# zx80_SD_12_smd_build006_6_STM32.net
KiCad netlist of a schematic drawn in EAGLE
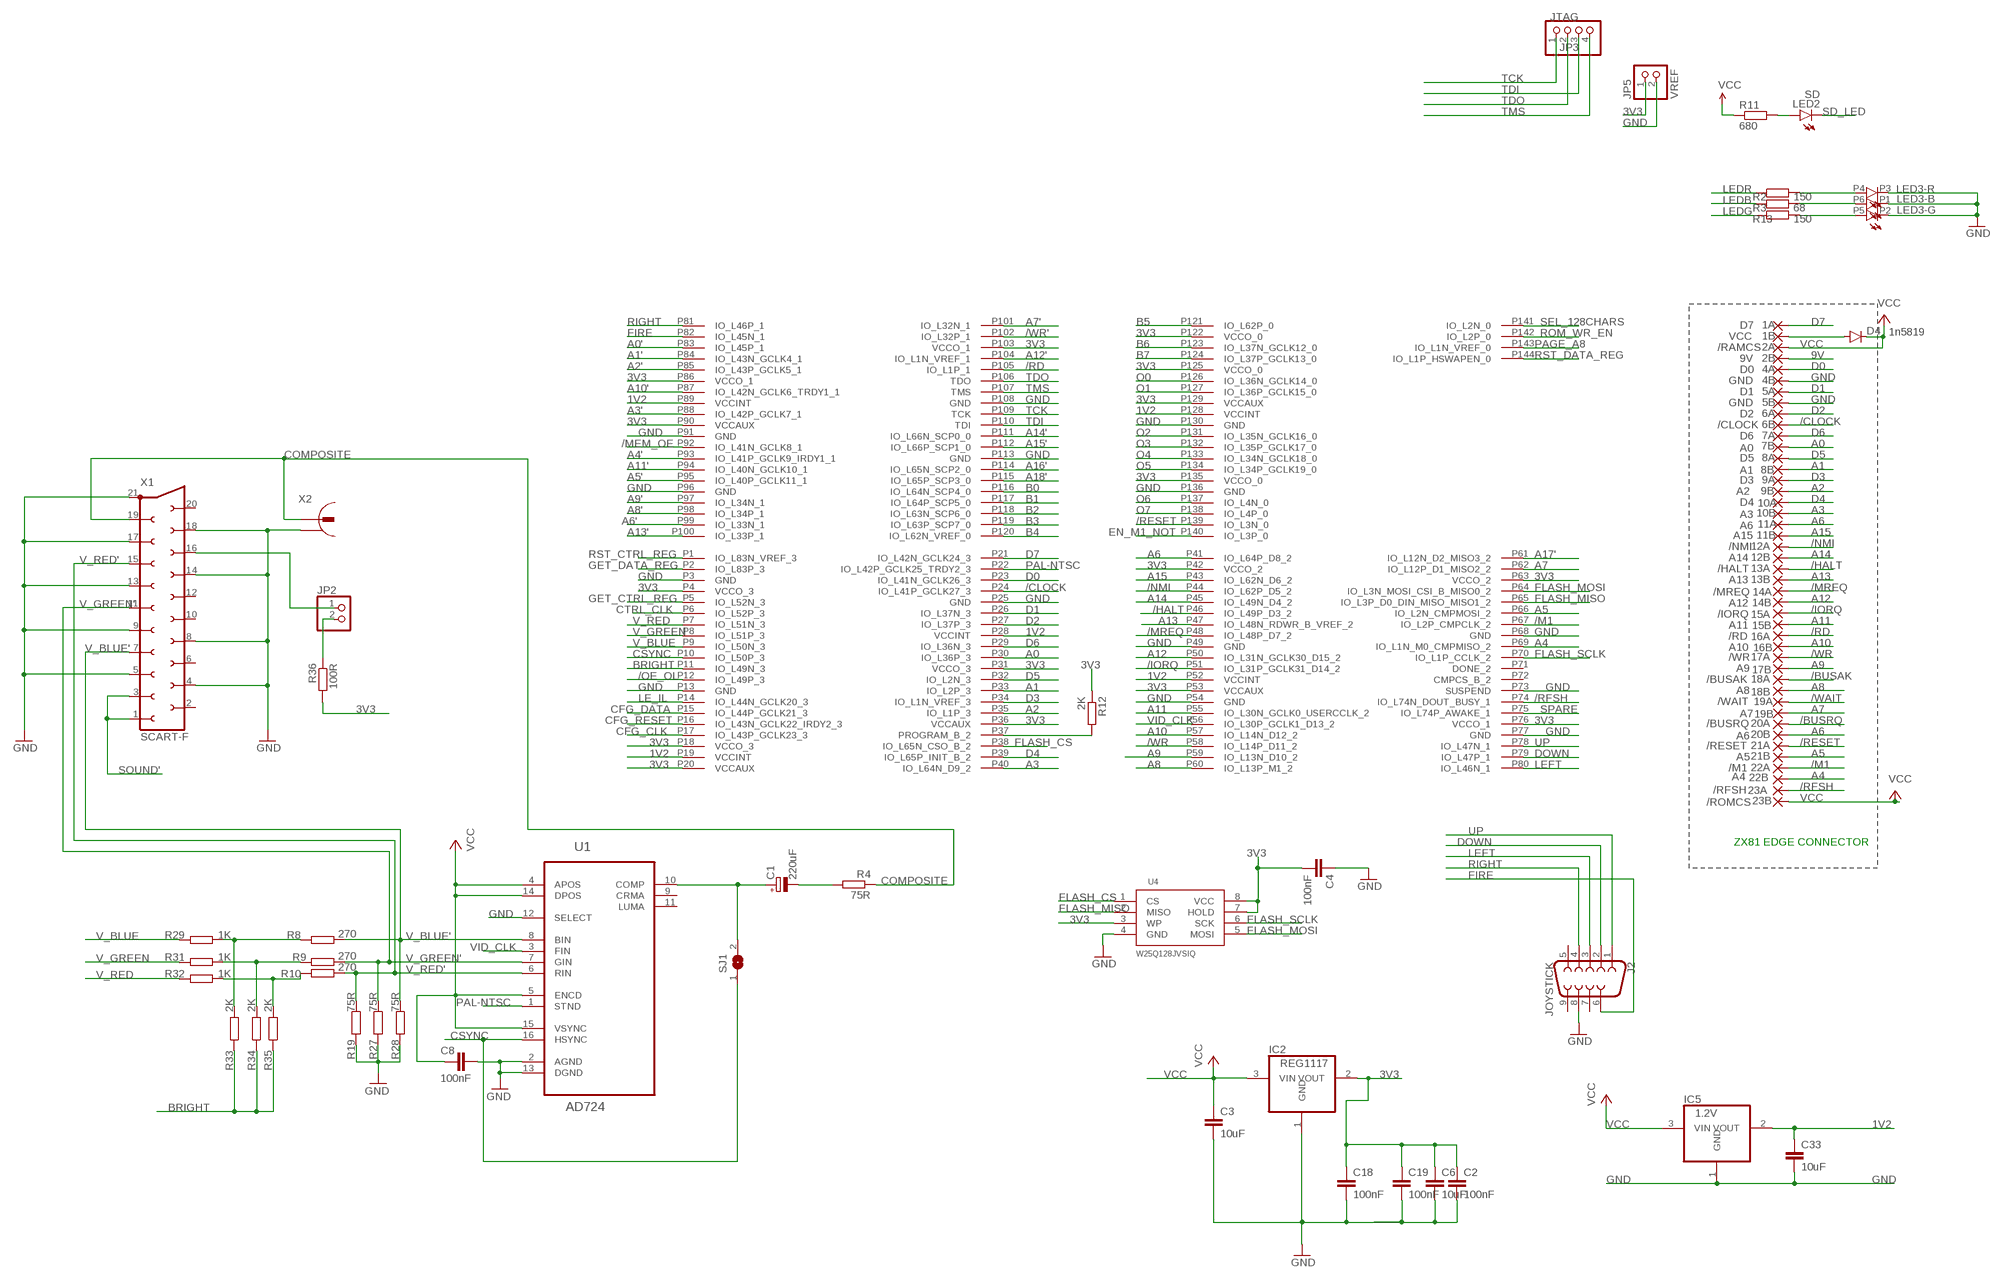
[diagram p0: schematic, sheet 1, part 1 of 2]
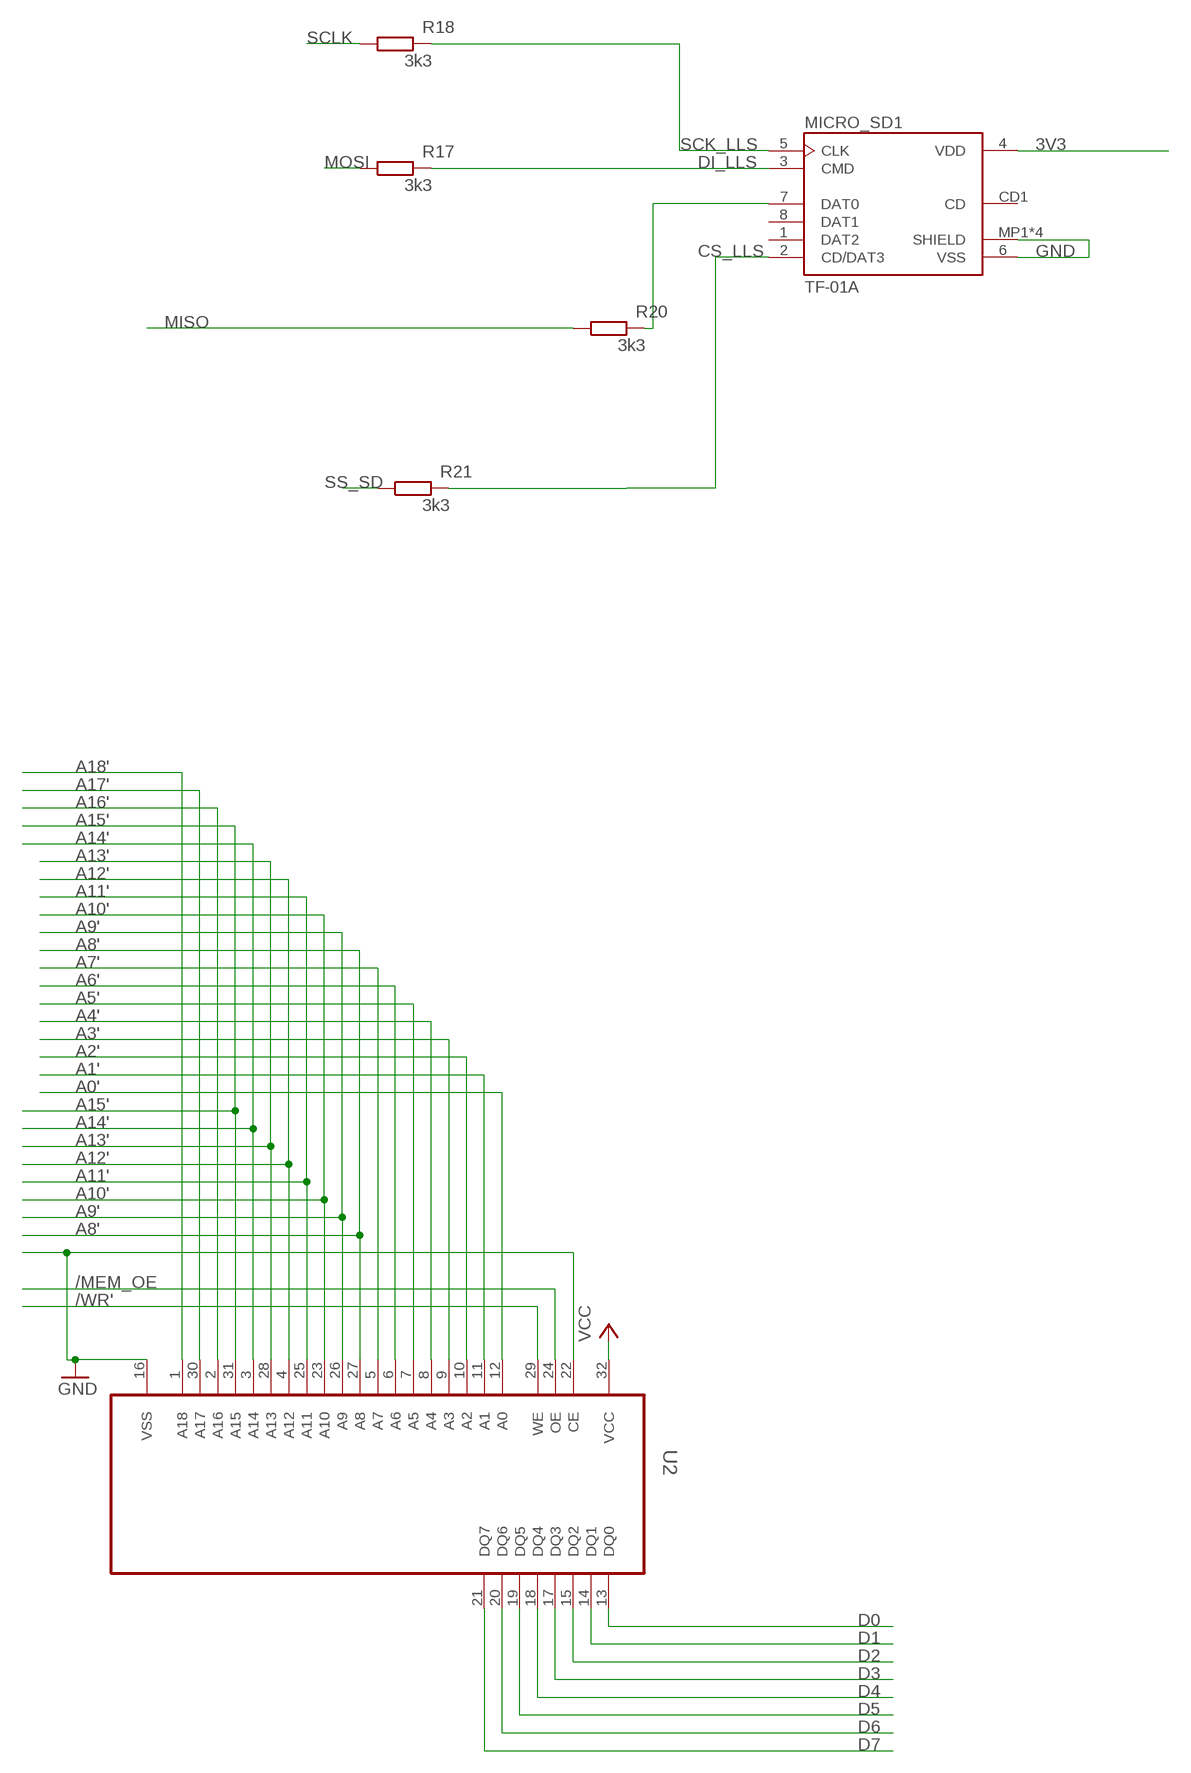
[diagram p1: schematic, sheet 1, part 2 of 2]
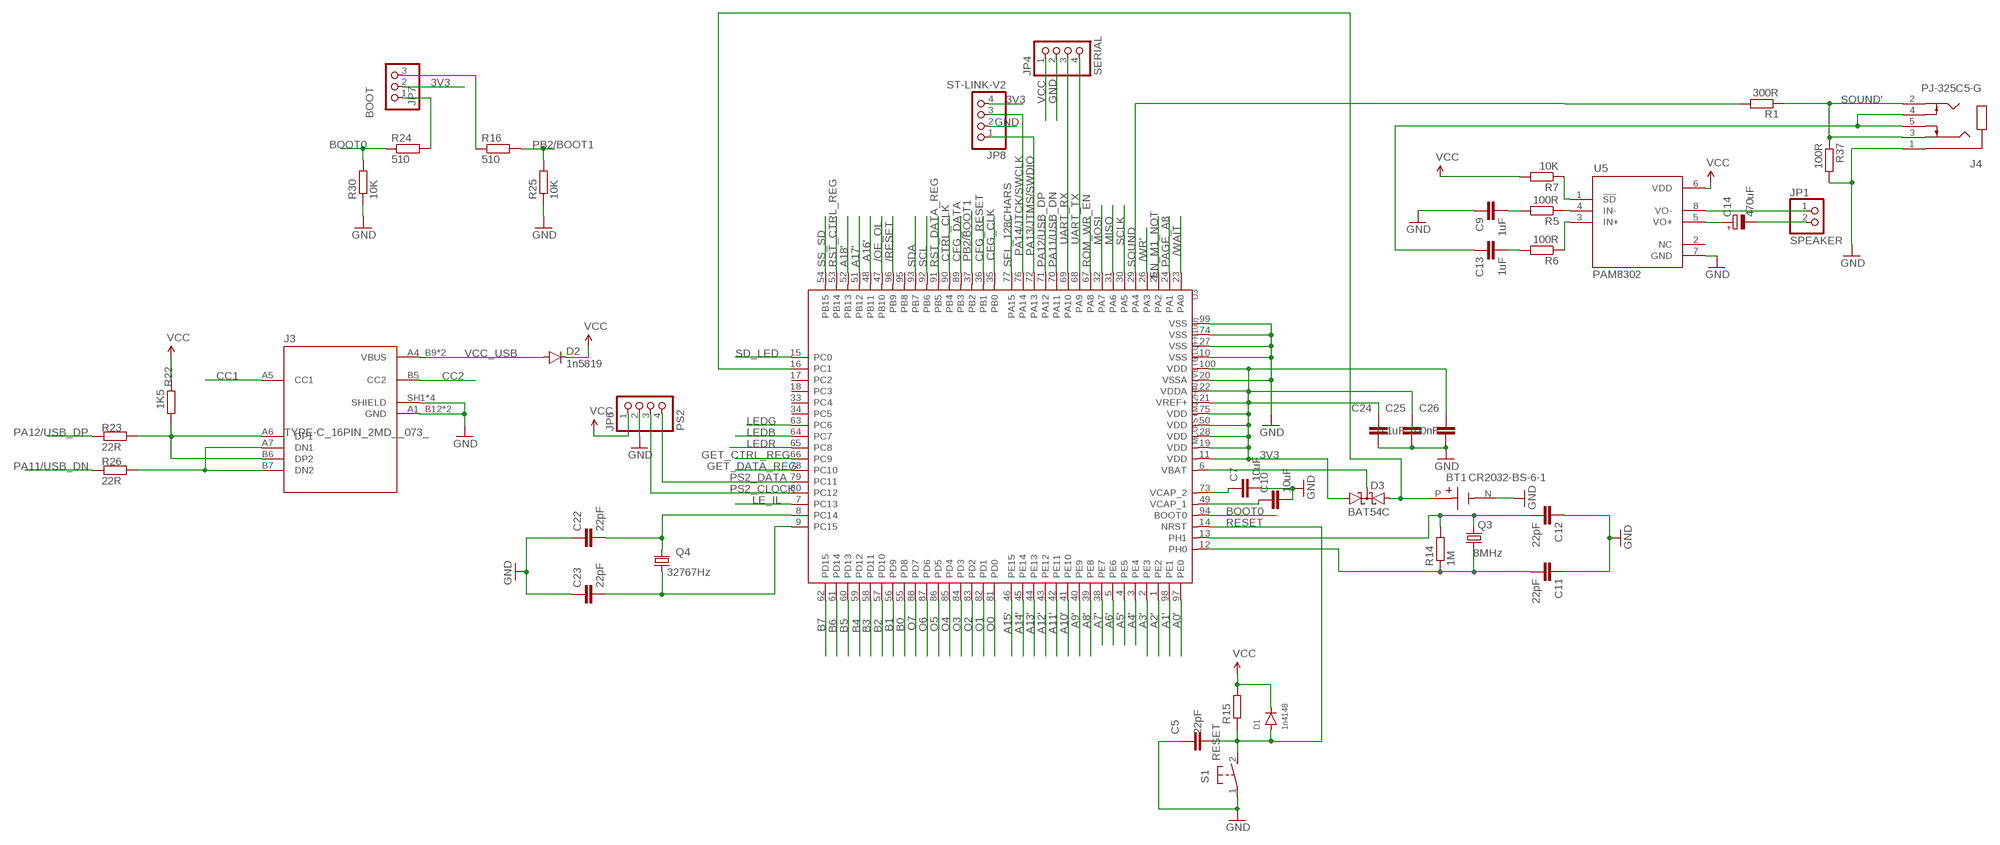
[diagram p2: schematic, sheet 2]

(export (version "E")
  (design (tool "Eeschema 10.0.6"))
  (components
    (comp (ref "1A")
      (value "D7")
      (footprint "eagle-import:EDGEPIN")
      (libsource (lib "eagle-import") (part "SMD2EDGEPIN"))
    )
    (comp (ref "1B")
      (value "VCC")
      (footprint "eagle-import:EDGEPIN")
      (libsource (lib "eagle-import") (part "SMD2EDGEPIN"))
    )
    (comp (ref "2A")
      (value "/RAMCS")
      (footprint "eagle-import:EDGEPIN")
      (libsource (lib "eagle-import") (part "SMD2EDGEPIN"))
    )
    (comp (ref "2B")
      (value "9V")
      (footprint "eagle-import:EDGEPIN")
      (libsource (lib "eagle-import") (part "SMD2EDGEPIN"))
    )
    (comp (ref "4A")
      (value "D0")
      (footprint "eagle-import:EDGEPIN")
      (libsource (lib "eagle-import") (part "SMD2EDGEPIN"))
    )
    (comp (ref "4B")
      (value "GND")
      (footprint "eagle-import:EDGEPIN")
      (libsource (lib "eagle-import") (part "SMD2EDGEPIN"))
    )
    (comp (ref "5A")
      (value "D1")
      (footprint "eagle-import:EDGEPIN")
      (libsource (lib "eagle-import") (part "SMD2EDGEPIN"))
    )
    (comp (ref "5B")
      (value "GND")
      (footprint "eagle-import:EDGEPIN")
      (libsource (lib "eagle-import") (part "SMD2EDGEPIN"))
    )
    (comp (ref "6A")
      (value "D2")
      (footprint "eagle-import:EDGEPIN")
      (libsource (lib "eagle-import") (part "SMD2EDGEPIN"))
    )
    (comp (ref "6B")
      (value "/CLOCK")
      (footprint "eagle-import:EDGEPIN")
      (libsource (lib "eagle-import") (part "SMD2EDGEPIN"))
    )
    (comp (ref "7A")
      (value "D6")
      (footprint "eagle-import:EDGEPIN")
      (libsource (lib "eagle-import") (part "SMD2EDGEPIN"))
    )
    (comp (ref "7B")
      (value "A0")
      (footprint "eagle-import:EDGEPIN")
      (libsource (lib "eagle-import") (part "SMD2EDGEPIN"))
    )
    (comp (ref "8A")
      (value "D5")
      (footprint "eagle-import:EDGEPIN")
      (libsource (lib "eagle-import") (part "SMD2EDGEPIN"))
    )
    (comp (ref "8B")
      (value "A1")
      (footprint "eagle-import:EDGEPIN")
      (libsource (lib "eagle-import") (part "SMD2EDGEPIN"))
    )
    (comp (ref "9A")
      (value "D3")
      (footprint "eagle-import:EDGEPIN")
      (libsource (lib "eagle-import") (part "SMD2EDGEPIN"))
    )
    (comp (ref "9B")
      (value "A2")
      (footprint "eagle-import:EDGEPIN")
      (libsource (lib "eagle-import") (part "SMD2EDGEPIN"))
    )
    (comp (ref "10A")
      (value "D4")
      (footprint "eagle-import:EDGEPIN")
      (libsource (lib "eagle-import") (part "SMD2EDGEPIN"))
    )
    (comp (ref "10B")
      (value "A3")
      (footprint "eagle-import:EDGEPIN")
      (libsource (lib "eagle-import") (part "SMD2EDGEPIN"))
    )
    (comp (ref "11A")
      (value "A6")
      (footprint "eagle-import:EDGEPIN")
      (libsource (lib "eagle-import") (part "SMD2EDGEPIN"))
    )
    (comp (ref "11B")
      (value "A15")
      (footprint "eagle-import:EDGEPIN")
      (libsource (lib "eagle-import") (part "SMD2EDGEPIN"))
    )
    (comp (ref "12A")
      (value "/NMI")
      (footprint "eagle-import:EDGEPIN")
      (libsource (lib "eagle-import") (part "SMD2EDGEPIN"))
    )
    (comp (ref "12B")
      (value "A14")
      (footprint "eagle-import:EDGEPIN")
      (libsource (lib "eagle-import") (part "SMD2EDGEPIN"))
    )
    (comp (ref "13A")
      (value "/HALT")
      (footprint "eagle-import:EDGEPIN")
      (libsource (lib "eagle-import") (part "SMD2EDGEPIN"))
    )
    (comp (ref "13B")
      (value "A13")
      (footprint "eagle-import:EDGEPIN")
      (libsource (lib "eagle-import") (part "SMD2EDGEPIN"))
    )
    (comp (ref "14A")
      (value "/MREQ")
      (footprint "eagle-import:EDGEPIN")
      (libsource (lib "eagle-import") (part "SMD2EDGEPIN"))
    )
    (comp (ref "14B")
      (value "A12")
      (footprint "eagle-import:EDGEPIN")
      (libsource (lib "eagle-import") (part "SMD2EDGEPIN"))
    )
    (comp (ref "15A")
      (value "/IORQ")
      (footprint "eagle-import:EDGEPIN")
      (libsource (lib "eagle-import") (part "SMD2EDGEPIN"))
    )
    (comp (ref "15B")
      (value "A11")
      (footprint "eagle-import:EDGEPIN")
      (libsource (lib "eagle-import") (part "SMD2EDGEPIN"))
    )
    (comp (ref "16A")
      (value "/RD")
      (footprint "eagle-import:EDGEPIN")
      (libsource (lib "eagle-import") (part "SMD2EDGEPIN"))
    )
    (comp (ref "16B")
      (value "A10")
      (footprint "eagle-import:EDGEPIN")
      (libsource (lib "eagle-import") (part "SMD2EDGEPIN"))
    )
    (comp (ref "17A")
      (value "/WR")
      (footprint "eagle-import:EDGEPIN")
      (libsource (lib "eagle-import") (part "SMD2EDGEPIN"))
    )
    (comp (ref "17B")
      (value "A9")
      (footprint "eagle-import:EDGEPIN")
      (libsource (lib "eagle-import") (part "SMD2EDGEPIN"))
    )
    (comp (ref "18A")
      (value "/BUSAK")
      (footprint "eagle-import:EDGEPIN")
      (libsource (lib "eagle-import") (part "SMD2EDGEPIN"))
    )
    (comp (ref "18B")
      (value "A8")
      (footprint "eagle-import:EDGEPIN")
      (libsource (lib "eagle-import") (part "SMD2EDGEPIN"))
    )
    (comp (ref "19A")
      (value "/WAIT")
      (footprint "eagle-import:EDGEPIN")
      (libsource (lib "eagle-import") (part "SMD2EDGEPIN"))
    )
    (comp (ref "19B")
      (value "A7")
      (footprint "eagle-import:EDGEPIN")
      (libsource (lib "eagle-import") (part "SMD2EDGEPIN"))
    )
    (comp (ref "20A")
      (value "/BUSRQ")
      (footprint "eagle-import:EDGEPIN")
      (libsource (lib "eagle-import") (part "SMD2EDGEPIN"))
    )
    (comp (ref "20B")
      (value "A6")
      (footprint "eagle-import:EDGEPIN")
      (libsource (lib "eagle-import") (part "SMD2EDGEPIN"))
    )
    (comp (ref "21A")
      (value "/RESET")
      (footprint "eagle-import:EDGEPIN")
      (libsource (lib "eagle-import") (part "SMD2EDGEPIN"))
    )
    (comp (ref "21B")
      (value "A5")
      (footprint "eagle-import:EDGEPIN")
      (libsource (lib "eagle-import") (part "SMD2EDGEPIN"))
    )
    (comp (ref "22A")
      (value "/M1")
      (footprint "eagle-import:EDGEPIN")
      (libsource (lib "eagle-import") (part "SMD2EDGEPIN"))
    )
    (comp (ref "22B")
      (value "A4")
      (footprint "eagle-import:EDGEPIN")
      (libsource (lib "eagle-import") (part "SMD2EDGEPIN"))
    )
    (comp (ref "23A")
      (value "/RFSH")
      (footprint "eagle-import:EDGEPIN")
      (libsource (lib "eagle-import") (part "SMD2EDGEPIN"))
    )
    (comp (ref "23B")
      (value "/ROMCS")
      (footprint "eagle-import:EDGEPIN")
      (libsource (lib "eagle-import") (part "SMD2EDGEPIN"))
    )
    (comp (ref "C1")
      (value "220uF")
      (footprint "eagle-import:UD-6,3X7,7_NICHICON")
      (libsource (lib "eagle-import") (part "CPOL-EUUD-6,3X7,7"))
    )
    (comp (ref "C2")
      (value "100nF")
      (footprint "eagle-import:C0603")
      (libsource (lib "eagle-import") (part "C-EUC0603"))
    )
    (comp (ref "C3")
      (value "10uF")
      (footprint "eagle-import:C0603")
      (libsource (lib "eagle-import") (part "C-EUC0603"))
    )
    (comp (ref "C4")
      (value "100nF")
      (footprint "eagle-import:C0603")
      (libsource (lib "eagle-import") (part "C-EUC0603"))
    )
    (comp (ref "C6")
      (value "10uF")
      (footprint "eagle-import:C0603")
      (libsource (lib "eagle-import") (part "C-EUC0603"))
    )
    (comp (ref "C8")
      (value "100nF")
      (footprint "eagle-import:C0603K")
      (libsource (lib "eagle-import") (part "C-EUC0603K"))
    )
    (comp (ref "C18")
      (value "100nF")
      (footprint "eagle-import:C0603")
      (libsource (lib "eagle-import") (part "C-EUC0603"))
    )
    (comp (ref "C19")
      (value "100nF")
      (footprint "eagle-import:C0603")
      (libsource (lib "eagle-import") (part "C-EUC0603"))
    )
    (comp (ref "C33")
      (value "10uF")
      (footprint "eagle-import:C0603")
      (libsource (lib "eagle-import") (part "C-EUC0603"))
    )
    (comp (ref "D4")
      (value "1n5819")
      (footprint "eagle-import:SOD323-W")
      (libsource (lib "eagle-import") (part "DIODE-SOD323-W"))
    )
    (comp (ref "IC2")
      (value "REG1117")
      (footprint "eagle-import:SOT223")
      (libsource (lib "eagle-import") (part "REG1117"))
    )
    (comp (ref "IC5")
      (value "1.2V")
      (footprint "eagle-import:SOT223")
      (fields (field (name "MPN") "REG1117"))
      (libsource (lib "eagle-import") (part "REG1117"))
    )
    (comp (ref "J2")
      (value "JOYSTICK")
      (footprint "eagle-import:DB9_MALE")
      (libsource (lib "eagle-import") (part "DB9MALE"))
    )
    (comp (ref "JP2")
      (value "PINHD-1X2")
      (footprint "eagle-import:1X02")
      (libsource (lib "eagle-import") (part "PINHD-1X2"))
    )
    (comp (ref "JP3")
      (value "JTAG")
      (footprint "eagle-import:1X04")
      (libsource (lib "eagle-import") (part "PINHD-1X4"))
    )
    (comp (ref "JP5")
      (value "VREF")
      (footprint "eagle-import:1X02")
      (libsource (lib "eagle-import") (part "PINHD-1X2"))
    )
    (comp (ref "LED2")
      (value "SD")
      (footprint "eagle-import:CHIPLED_0805")
      (libsource (lib "eagle-import") (part "LEDCHIPLED_0805"))
    )
    (comp (ref "LED3")
      (value "STATUS")
      (footprint "eagle-import:3535-PLCC6")
      (libsource (lib "eagle-import") (part "3535RGB3535RGB"))
    )
    (comp (ref "MICRO_SD1")
      (value "TF-01A")
      (footprint "eagle-import:TF-01A")
      (fields (field (name "MF") "HRO Electronics Co., Ltd."))
      (libsource (lib "eagle-import") (part "TF-01A"))
    )
    (comp (ref "R2")
      (value "150")
      (footprint "eagle-import:R0603")
      (libsource (lib "eagle-import") (part "R-EU_R0603"))
    )
    (comp (ref "R3")
      (value "68")
      (footprint "eagle-import:R0603")
      (libsource (lib "eagle-import") (part "R-EU_R0603"))
    )
    (comp (ref "R4")
      (value "75R")
      (footprint "eagle-import:R0603")
      (libsource (lib "eagle-import") (part "R-EU_R0603"))
    )
    (comp (ref "R8")
      (value "270")
      (footprint "eagle-import:R0603")
      (libsource (lib "eagle-import") (part "R-EU_R0603"))
    )
    (comp (ref "R9")
      (value "270")
      (footprint "eagle-import:R0603")
      (libsource (lib "eagle-import") (part "R-EU_R0603"))
    )
    (comp (ref "R10")
      (value "270")
      (footprint "eagle-import:R0603")
      (libsource (lib "eagle-import") (part "R-EU_R0603"))
    )
    (comp (ref "R11")
      (value "680")
      (footprint "eagle-import:R0603")
      (libsource (lib "eagle-import") (part "R-EU_R0603"))
    )
    (comp (ref "R12")
      (value "2K")
      (footprint "eagle-import:R0402")
      (libsource (lib "eagle-import") (part "R-EU_R0402"))
    )
    (comp (ref "R13")
      (value "150")
      (footprint "eagle-import:R0603")
      (libsource (lib "eagle-import") (part "R-EU_R0603"))
    )
    (comp (ref "R17")
      (value "3k3")
      (footprint "eagle-import:R0603")
      (libsource (lib "eagle-import") (part "R-EU_R0603"))
    )
    (comp (ref "R18")
      (value "3k3")
      (footprint "eagle-import:R0603")
      (libsource (lib "eagle-import") (part "R-EU_R0603"))
    )
    (comp (ref "R19")
      (value "75R")
      (footprint "eagle-import:R0603")
      (libsource (lib "eagle-import") (part "R-EU_R0603"))
    )
    (comp (ref "R20")
      (value "3k3")
      (footprint "eagle-import:R0603")
      (libsource (lib "eagle-import") (part "R-EU_R0603"))
    )
    (comp (ref "R21")
      (value "3k3")
      (footprint "eagle-import:R0603")
      (libsource (lib "eagle-import") (part "R-EU_R0603"))
    )
    (comp (ref "R27")
      (value "75R")
      (footprint "eagle-import:R0603")
      (libsource (lib "eagle-import") (part "R-EU_R0603"))
    )
    (comp (ref "R28")
      (value "75R")
      (footprint "eagle-import:R0603")
      (libsource (lib "eagle-import") (part "R-EU_R0603"))
    )
    (comp (ref "R29")
      (value "1K")
      (footprint "eagle-import:R0402")
      (libsource (lib "eagle-import") (part "R-EU_R0402"))
    )
    (comp (ref "R31")
      (value "1K")
      (footprint "eagle-import:R0402")
      (libsource (lib "eagle-import") (part "R-EU_R0402"))
    )
    (comp (ref "R32")
      (value "1K")
      (footprint "eagle-import:R0402")
      (libsource (lib "eagle-import") (part "R-EU_R0402"))
    )
    (comp (ref "R33")
      (value "2K")
      (footprint "eagle-import:R0402")
      (libsource (lib "eagle-import") (part "R-EU_R0402"))
    )
    (comp (ref "R34")
      (value "2K")
      (footprint "eagle-import:R0402")
      (libsource (lib "eagle-import") (part "R-EU_R0402"))
    )
    (comp (ref "R35")
      (value "2K")
      (footprint "eagle-import:R0402")
      (libsource (lib "eagle-import") (part "R-EU_R0402"))
    )
    (comp (ref "R36")
      (value "100R")
      (footprint "eagle-import:R0603")
      (libsource (lib "eagle-import") (part "R-EU_R0603"))
    )
    (comp (ref "SJ1") (value "SJ") (footprint "eagle-import:SJ") (libsource (lib "eagle-import") (part "SJ")))
    (comp (ref "U1")
      (value "AD724")
      (footprint "eagle-import:SOIC127P1032X265-16N")
      (fields (field (name "MF") "Analog Devices") (field (name "MP") "AD724JR"))
      (libsource (lib "eagle-import") (part "AD724JRZ"))
    )
    (comp (ref "U2")
      (value "AS6C4008")
      (footprint "eagle-import:SOP32-5")
      (libsource (lib "eagle-import") (part "AS6C4008-55SINSOP5"))
    )
    (comp (ref "U4")
      (value "W25Q128JVSIQ")
      (footprint "eagle-import:SO08-EIAJ")
      (libsource (lib "eagle-import") (part "SPI_FLASH-X25XXSMD1"))
    )
    (comp (ref "U6")
      (value "XC6SLX9-2TQG144C")
      (footprint "eagle-import:TQ144")
      (fields (field (name "MF") "Xilinx Inc."))
      (libsource (lib "eagle-import") (part "XC6SLX9-2TQG144C"))
    )
    (comp (ref "X1")
      (value "SCART-F")
      (footprint "eagle-import:SCART-F")
      (libsource (lib "eagle-import") (part "SCART-F"))
    )
    (comp (ref "X2")
      (value "CON-CONRAD_736880-2P")
      (footprint "eagle-import:3P")
      (libsource (lib "eagle-import") (part "CON-CONRAD_736880-2P"))
    )
    (comp (ref "BT1")
      (value "CR2032-BS-6-1")
      (footprint "eagle-import:BAT_CR2032-BS-6-1")
      (fields (field (name "MF") "Shenzhen Q&J Electronics Co. Ltd"))
      (libsource (lib "eagle-import") (part "CR2032-BS-6-1"))
    )
    (comp (ref "C5")
      (value "22pF")
      (footprint "eagle-import:C0603")
      (libsource (lib "eagle-import") (part "C-EUC0603"))
    )
    (comp (ref "C7")
      (value "10uF")
      (footprint "eagle-import:C0603")
      (libsource (lib "eagle-import") (part "C-EUC0603"))
    )
    (comp (ref "C9")
      (value "1uF")
      (footprint "eagle-import:C0603")
      (libsource (lib "eagle-import") (part "C-EUC0603"))
    )
    (comp (ref "C10")
      (value "10uF")
      (footprint "eagle-import:C0603")
      (libsource (lib "eagle-import") (part "C-EUC0603"))
    )
    (comp (ref "C11")
      (value "22pF")
      (footprint "eagle-import:C0603")
      (libsource (lib "eagle-import") (part "C-EUC0603"))
    )
    (comp (ref "C12")
      (value "22pF")
      (footprint "eagle-import:C0603")
      (libsource (lib "eagle-import") (part "C-EUC0603"))
    )
    (comp (ref "C13")
      (value "1uF")
      (footprint "eagle-import:C0603")
      (libsource (lib "eagle-import") (part "C-EUC0603"))
    )
    (comp (ref "C14")
      (value "470uF")
      (footprint "eagle-import:UD-6,3X7,7_NICHICON")
      (libsource (lib "eagle-import") (part "CPOL-EUUD-6,3X7,7"))
    )
    (comp (ref "C22")
      (value "22pF")
      (footprint "eagle-import:C0603")
      (libsource (lib "eagle-import") (part "C-EUC0603"))
    )
    (comp (ref "C23")
      (value "22pF")
      (footprint "eagle-import:C0603")
      (libsource (lib "eagle-import") (part "C-EUC0603"))
    )
    (comp (ref "C24")
      (value "0.1uF")
      (footprint "eagle-import:C0603")
      (libsource (lib "eagle-import") (part "C-EUC0603"))
    )
    (comp (ref "C25")
      (value "0.1uF")
      (footprint "eagle-import:C0603")
      (libsource (lib "eagle-import") (part "C-EUC0603"))
    )
    (comp (ref "C26")
      (value "100nF")
      (footprint "eagle-import:C0603")
      (libsource (lib "eagle-import") (part "C-EUC0603"))
    )
    (comp (ref "D1")
      (value "1n4148")
      (footprint "eagle-import:SOD123")
      (libsource (lib "eagle-import") (part "DIODE-SOD123"))
    )
    (comp (ref "D2")
      (value "1n5819")
      (footprint "eagle-import:SOD323-W")
      (libsource (lib "eagle-import") (part "DIODE-SOD323-W"))
    )
    (comp (ref "D3")
      (value "BAT54C")
      (footprint "eagle-import:SOT23")
      (libsource (lib "eagle-import") (part "BAT54C"))
    )
    (comp (ref "J3")
      (value "TYPE-C_16PIN_2MD__073_")
      (footprint "eagle-import:SHOUHAN_TYPE-C_16PIN_2MD__073_")
      (fields (field (name "MF") "Shouhan") (field (name "MP") "TYPE-C 16PIN 2MD (073)"))
      (libsource (lib "eagle-import") (part "TYPE-C_16PIN_2MD__073_"))
    )
    (comp (ref "J4")
      (value "PJ-325C5-G")
      (footprint "eagle-import:XKB_PJ-325C5-G")
      (fields (field (name "MF") "XKB Connection"))
      (libsource (lib "eagle-import") (part "PJ-325C5-G"))
    )
    (comp (ref "JP1")
      (value "SPEAKER")
      (footprint "eagle-import:1X02")
      (libsource (lib "eagle-import") (part "PINHD-1X2"))
    )
    (comp (ref "JP4")
      (value "SERIAL")
      (footprint "eagle-import:1X04")
      (libsource (lib "eagle-import") (part "PINHD-1X4"))
    )
    (comp (ref "JP6")
      (value "PS2")
      (footprint "eagle-import:1X04")
      (libsource (lib "eagle-import") (part "PINHD-1X4"))
    )
    (comp (ref "JP7")
      (value "BOOT")
      (footprint "eagle-import:1X03")
      (libsource (lib "eagle-import") (part "PINHD-1X3"))
    )
    (comp (ref "JP8")
      (value "ST-LINK-V2")
      (footprint "eagle-import:1X04")
      (libsource (lib "eagle-import") (part "PINHD-1X4"))
    )
    (comp (ref "Q3")
      (value "8MHz")
      (footprint "eagle-import:3.2X2.5_KX-7")
      (libsource (lib "eagle-import") (part "KX-7"))
    )
    (comp (ref "Q4")
      (value "32767Hz")
      (footprint "eagle-import:3.2X1.5")
      (libsource (lib "eagle-import") (part "KX-327-NHT"))
    )
    (comp (ref "R1")
      (value "300R")
      (footprint "eagle-import:R0603")
      (libsource (lib "eagle-import") (part "R-EU_R0603"))
    )
    (comp (ref "R5")
      (value "100R")
      (footprint "eagle-import:R0603")
      (libsource (lib "eagle-import") (part "R-EU_R0603"))
    )
    (comp (ref "R6")
      (value "100R")
      (footprint "eagle-import:R0603")
      (libsource (lib "eagle-import") (part "R-EU_R0603"))
    )
    (comp (ref "R7")
      (value "10K")
      (footprint "eagle-import:R0603")
      (libsource (lib "eagle-import") (part "R-EU_R0603"))
    )
    (comp (ref "R14")
      (value "1M")
      (footprint "eagle-import:R0402")
      (libsource (lib "eagle-import") (part "R-EU_R0402"))
    )
    (comp (ref "R15")
      (value "3k3")
      (footprint "eagle-import:R0603")
      (libsource (lib "eagle-import") (part "R-EU_R0603"))
    )
    (comp (ref "R16")
      (value "510")
      (footprint "eagle-import:R0603")
      (libsource (lib "eagle-import") (part "R-EU_R0603"))
    )
    (comp (ref "R22")
      (value "1K5")
      (footprint "eagle-import:R0603")
      (libsource (lib "eagle-import") (part "R-EU_R0603"))
    )
    (comp (ref "R23")
      (value "22R")
      (footprint "eagle-import:R0603")
      (libsource (lib "eagle-import") (part "R-EU_R0603"))
    )
    (comp (ref "R24")
      (value "510")
      (footprint "eagle-import:R0603")
      (libsource (lib "eagle-import") (part "R-EU_R0603"))
    )
    (comp (ref "R25")
      (value "10K")
      (footprint "eagle-import:R0603")
      (libsource (lib "eagle-import") (part "R-EU_R0603"))
    )
    (comp (ref "R26")
      (value "22R")
      (footprint "eagle-import:R0603")
      (libsource (lib "eagle-import") (part "R-EU_R0603"))
    )
    (comp (ref "R30")
      (value "10K")
      (footprint "eagle-import:R0603")
      (libsource (lib "eagle-import") (part "R-EU_R0603"))
    )
    (comp (ref "R37")
      (value "100R")
      (footprint "eagle-import:R0603")
      (libsource (lib "eagle-import") (part "R-EU_R0603"))
    )
    (comp (ref "S1")
      (value "RESET")
      (footprint "eagle-import:B3F-31XX")
      (fields (field (name "MPN") "B3F-3100"))
      (libsource (lib "eagle-import") (part "31-XX"))
    )
    (comp (ref "U3")
      (value "MCU-STM32F407VET6(LQFP100)")
      (footprint "eagle-import:LQFP100-0.5-13.8X13.8MM")
      (fields (field (name "MF") "STMicroelectronics") (field (name "MP") "STM32F407VET6"))
      (libsource (lib "eagle-import") (part "MCU-STM32F407VET6(LQFP100)"))
    )
    (comp (ref "U5")
      (value "PAM8302")
      (footprint "eagle-import:SOIC127P600X170-8N")
      (fields (field (name "MF") "Diodes Inc.") (field (name "MP") "PAM8302AADCR"))
      (libsource (lib "eagle-import") (part "PAM8302AADCR"))
    )
  )
  (nets
    (net (code "1") (name "1V2") (class "Default")
      (node (ref "C33") (pin "1") (pinfunction "1_1") (pintype "passive"))
      (node (ref "IC5") (pin "2") (pinfunction "VOUT_2") (pintype "output"))
      (node (ref "U6") (pin "P128") (pinfunction "VCCINT_P128") (pintype "bidirectional"))
      (node (ref "U6") (pin "P19") (pinfunction "VCCINT_P19") (pintype "bidirectional"))
      (node (ref "U6") (pin "P28") (pinfunction "VCCINT_P28") (pintype "bidirectional"))
      (node (ref "U6") (pin "P52") (pinfunction "VCCINT_P52") (pintype "bidirectional"))
      (node (ref "U6") (pin "P89") (pinfunction "VCCINT_P89") (pintype "bidirectional"))
    )
    (net (code "2") (name "3V3") (class "Default")
      (node (ref "C18") (pin "1") (pinfunction "1_1") (pintype "passive"))
      (node (ref "C19") (pin "1") (pinfunction "1_1") (pintype "passive"))
      (node (ref "C2") (pin "1") (pinfunction "1_1") (pintype "passive"))
      (node (ref "C24") (pin "1") (pinfunction "1_1") (pintype "passive"))
      (node (ref "C25") (pin "1") (pinfunction "1_1") (pintype "passive"))
      (node (ref "C26") (pin "1") (pinfunction "1_1") (pintype "passive"))
      (node (ref "C4") (pin "2") (pinfunction "2_2") (pintype "passive"))
      (node (ref "C6") (pin "1") (pinfunction "1_1") (pintype "passive"))
      (node (ref "D3") (pin "1") (pinfunction "A1_1") (pintype "passive"))
      (node (ref "IC2") (pin "2") (pinfunction "VOUT_2") (pintype "output"))
      (node (ref "JP5") (pin "1") (pinfunction "1_1") (pintype "passive"))
      (node (ref "JP7") (pin "2") (pinfunction "2_2") (pintype "passive"))
      (node (ref "JP8") (pin "4") (pinfunction "4_4") (pintype "passive"))
      (node (ref "MICRO_SD1") (pin "4") (pinfunction "VDD_4") (pintype "power_in"))
      (node (ref "R12") (pin "1") (pinfunction "1_1") (pintype "passive"))
      (node (ref "R36") (pin "2") (pinfunction "2_2") (pintype "passive"))
      (node (ref "U3") (pin "100") (pinfunction "VDD_100") (pintype "bidirectional"))
      (node (ref "U3") (pin "11") (pinfunction "VDD_11") (pintype "bidirectional"))
      (node (ref "U3") (pin "19") (pinfunction "VDD_19") (pintype "bidirectional"))
      (node (ref "U3") (pin "21") (pinfunction "VREF+_21") (pintype "bidirectional"))
      (node (ref "U3") (pin "22") (pinfunction "VDDA_22") (pintype "bidirectional"))
      (node (ref "U3") (pin "28") (pinfunction "VDD_28") (pintype "bidirectional"))
      (node (ref "U3") (pin "50") (pinfunction "VDD_50") (pintype "bidirectional"))
      (node (ref "U3") (pin "75") (pinfunction "VDD_75") (pintype "bidirectional"))
      (node (ref "U4") (pin "3") (pinfunction "WP_3") (pintype "bidirectional"))
      (node (ref "U4") (pin "7") (pinfunction "HOLD_7") (pintype "bidirectional"))
      (node (ref "U4") (pin "8") (pinfunction "VCC_8") (pintype "power_in"))
      (node (ref "U6") (pin "P103") (pinfunction "VCCO_1_P103") (pintype "bidirectional"))
      (node (ref "U6") (pin "P122") (pinfunction "VCCO_0_P122") (pintype "bidirectional"))
      (node (ref "U6") (pin "P125") (pinfunction "VCCO_0_P125") (pintype "bidirectional"))
      (node (ref "U6") (pin "P129") (pinfunction "VCCAUX_P129") (pintype "bidirectional"))
      (node (ref "U6") (pin "P135") (pinfunction "VCCO_0_P135") (pintype "bidirectional"))
      (node (ref "U6") (pin "P18") (pinfunction "VCCO_3_P18") (pintype "bidirectional"))
      (node (ref "U6") (pin "P20") (pinfunction "VCCAUX_P20") (pintype "bidirectional"))
      (node (ref "U6") (pin "P31") (pinfunction "VCCO_3_P31") (pintype "bidirectional"))
      (node (ref "U6") (pin "P36") (pinfunction "VCCAUX_P36") (pintype "bidirectional"))
      (node (ref "U6") (pin "P4") (pinfunction "VCCO_3_P4") (pintype "bidirectional"))
      (node (ref "U6") (pin "P42") (pinfunction "VCCO_2_P42") (pintype "bidirectional"))
      (node (ref "U6") (pin "P53") (pinfunction "VCCAUX_P53") (pintype "bidirectional"))
      (node (ref "U6") (pin "P63") (pinfunction "VCCO_2_P63") (pintype "bidirectional"))
      (node (ref "U6") (pin "P76") (pinfunction "VCCO_1_P76") (pintype "bidirectional"))
      (node (ref "U6") (pin "P86") (pinfunction "VCCO_1_P86") (pintype "bidirectional"))
      (node (ref "U6") (pin "P90") (pinfunction "VCCAUX_P90") (pintype "bidirectional"))
    )
    (net (code "3") (name "9V") (class "Default")
      (node (ref "2B") (pin "1") (pinfunction "P_1") (pintype "passive"))
    )
    (net (code "4") (name "A0") (class "Default")
      (node (ref "7B") (pin "1") (pinfunction "P_1") (pintype "passive"))
      (node (ref "U6") (pin "P30") (pinfunction "IO_L36P_3_P30") (pintype "bidirectional"))
    )
    (net (code "5") (name "A0'") (class "Default")
      (node (ref "U2") (pin "12") (pinfunction "A0_12") (pintype "input"))
      (node (ref "U3") (pin "97") (pinfunction "PE0_97") (pintype "bidirectional"))
      (node (ref "U6") (pin "P83") (pinfunction "IO_L45P_1_P83") (pintype "bidirectional"))
    )
    (net (code "6") (name "A1") (class "Default")
      (node (ref "8B") (pin "1") (pinfunction "P_1") (pintype "passive"))
      (node (ref "U6") (pin "P33") (pinfunction "IO_L2P_3_P33") (pintype "bidirectional"))
    )
    (net (code "7") (name "A1'") (class "Default")
      (node (ref "U2") (pin "11") (pinfunction "A1_11") (pintype "input"))
      (node (ref "U3") (pin "98") (pinfunction "PE1_98") (pintype "bidirectional"))
      (node (ref "U6") (pin "P84") (pinfunction "IO_L43N_GCLK4_1_P84") (pintype "bidirectional"))
    )
    (net (code "8") (name "A2") (class "Default")
      (node (ref "9B") (pin "1") (pinfunction "P_1") (pintype "passive"))
      (node (ref "U6") (pin "P35") (pinfunction "IO_L1P_3_P35") (pintype "bidirectional"))
    )
    (net (code "9") (name "A2'") (class "Default")
      (node (ref "U2") (pin "10") (pinfunction "A2_10") (pintype "input"))
      (node (ref "U3") (pin "1") (pinfunction "PE2_1") (pintype "bidirectional"))
      (node (ref "U6") (pin "P85") (pinfunction "IO_L43P_GCLK5_1_P85") (pintype "bidirectional"))
    )
    (net (code "10") (name "A3") (class "Default")
      (node (ref "10B") (pin "1") (pinfunction "P_1") (pintype "passive"))
      (node (ref "U6") (pin "P40") (pinfunction "IO_L64N_D9_2_P40") (pintype "bidirectional"))
    )
    (net (code "11") (name "A3'") (class "Default")
      (node (ref "U2") (pin "9") (pinfunction "A3_9") (pintype "input"))
      (node (ref "U3") (pin "2") (pinfunction "PE3_2") (pintype "bidirectional"))
      (node (ref "U6") (pin "P88") (pinfunction "IO_L42P_GCLK7_1_P88") (pintype "bidirectional"))
    )
    (net (code "12") (name "A4") (class "Default")
      (node (ref "22B") (pin "1") (pinfunction "P_1") (pintype "passive"))
      (node (ref "U6") (pin "P69") (pinfunction "IO_L1N_M0_CMPMISO_2_P69") (pintype "bidirectional"))
    )
    (net (code "13") (name "A4'") (class "Default")
      (node (ref "U2") (pin "8") (pinfunction "A4_8") (pintype "input"))
      (node (ref "U3") (pin "3") (pinfunction "PE4_3") (pintype "bidirectional"))
      (node (ref "U6") (pin "P93") (pinfunction "IO_L41P_GCLK9_IRDY1_1_P93") (pintype "bidirectional"))
    )
    (net (code "14") (name "A5") (class "Default")
      (node (ref "21B") (pin "1") (pinfunction "P_1") (pintype "passive"))
      (node (ref "U6") (pin "P66") (pinfunction "IO_L2N_CMPMOSI_2_P66") (pintype "bidirectional"))
    )
    (net (code "15") (name "A5'") (class "Default")
      (node (ref "U2") (pin "7") (pinfunction "A5_7") (pintype "input"))
      (node (ref "U3") (pin "4") (pinfunction "PE5_4") (pintype "bidirectional"))
      (node (ref "U6") (pin "P95") (pinfunction "IO_L40P_GCLK11_1_P95") (pintype "bidirectional"))
    )
    (net (code "16") (name "A6") (class "Default")
      (node (ref "11A") (pin "1") (pinfunction "P_1") (pintype "passive"))
      (node (ref "20B") (pin "1") (pinfunction "P_1") (pintype "passive"))
      (node (ref "U6") (pin "P41") (pinfunction "IO_L64P_D8_2_P41") (pintype "bidirectional"))
    )
    (net (code "17") (name "A6'") (class "Default")
      (node (ref "U2") (pin "6") (pinfunction "A6_6") (pintype "input"))
      (node (ref "U3") (pin "5") (pinfunction "PE6_5") (pintype "bidirectional"))
      (node (ref "U6") (pin "P99") (pinfunction "IO_L33N_1_P99") (pintype "bidirectional"))
    )
    (net (code "18") (name "A7") (class "Default")
      (node (ref "19B") (pin "1") (pinfunction "P_1") (pintype "passive"))
      (node (ref "U6") (pin "P62") (pinfunction "IO_L12P_D1_MISO2_2_P62") (pintype "bidirectional"))
    )
    (net (code "19") (name "A7'") (class "Default")
      (node (ref "U2") (pin "5") (pinfunction "A7_5") (pintype "input"))
      (node (ref "U3") (pin "38") (pinfunction "PE7_38") (pintype "bidirectional"))
      (node (ref "U6") (pin "P101") (pinfunction "IO_L32N_1_P101") (pintype "bidirectional"))
    )
    (net (code "20") (name "A8") (class "Default")
      (node (ref "18B") (pin "1") (pinfunction "P_1") (pintype "passive"))
      (node (ref "U6") (pin "P60") (pinfunction "IO_L13P_M1_2_P60") (pintype "bidirectional"))
    )
    (net (code "21") (name "A8'") (class "Default")
      (node (ref "U2") (pin "27") (pinfunction "A8_27") (pintype "input"))
      (node (ref "U3") (pin "39") (pinfunction "PE8_39") (pintype "bidirectional"))
      (node (ref "U6") (pin "P98") (pinfunction "IO_L34P_1_P98") (pintype "bidirectional"))
    )
    (net (code "22") (name "A9") (class "Default")
      (node (ref "17B") (pin "1") (pinfunction "P_1") (pintype "passive"))
      (node (ref "U6") (pin "P59") (pinfunction "IO_L13N_D10_2_P59") (pintype "bidirectional"))
    )
    (net (code "23") (name "A9'") (class "Default")
      (node (ref "U2") (pin "26") (pinfunction "A9_26") (pintype "input"))
      (node (ref "U3") (pin "40") (pinfunction "PE9_40") (pintype "bidirectional"))
      (node (ref "U6") (pin "P97") (pinfunction "IO_L34N_1_P97") (pintype "bidirectional"))
    )
    (net (code "24") (name "A10") (class "Default")
      (node (ref "16B") (pin "1") (pinfunction "P_1") (pintype "passive"))
      (node (ref "U6") (pin "P57") (pinfunction "IO_L14N_D12_2_P57") (pintype "bidirectional"))
    )
    (net (code "25") (name "A10'") (class "Default")
      (node (ref "U2") (pin "23") (pinfunction "A10_23") (pintype "input"))
      (node (ref "U3") (pin "41") (pinfunction "PE10_41") (pintype "bidirectional"))
      (node (ref "U6") (pin "P87") (pinfunction "IO_L42N_GCLK6_TRDY1_1_P87") (pintype "bidirectional"))
    )
    (net (code "26") (name "A11") (class "Default")
      (node (ref "15B") (pin "1") (pinfunction "P_1") (pintype "passive"))
      (node (ref "U6") (pin "P55") (pinfunction "IO_L30N_GCLK0_USERCCLK_2_P55") (pintype "bidirectional"))
    )
    (net (code "27") (name "A11'") (class "Default")
      (node (ref "U2") (pin "25") (pinfunction "A11_25") (pintype "input"))
      (node (ref "U3") (pin "42") (pinfunction "PE11_42") (pintype "bidirectional"))
      (node (ref "U6") (pin "P94") (pinfunction "IO_L40N_GCLK10_1_P94") (pintype "bidirectional"))
    )
    (net (code "28") (name "A12") (class "Default")
      (node (ref "14B") (pin "1") (pinfunction "P_1") (pintype "passive"))
      (node (ref "U6") (pin "P50") (pinfunction "IO_L31N_GCLK30_D15_2_P50") (pintype "bidirectional"))
    )
    (net (code "29") (name "A12'") (class "Default")
      (node (ref "U2") (pin "4") (pinfunction "A12_4") (pintype "input"))
      (node (ref "U3") (pin "43") (pinfunction "PE12_43") (pintype "bidirectional"))
      (node (ref "U6") (pin "P104") (pinfunction "IO_L1N_VREF_1_P104") (pintype "bidirectional"))
    )
    (net (code "30") (name "A13") (class "Default")
      (node (ref "13B") (pin "1") (pinfunction "P_1") (pintype "passive"))
      (node (ref "U6") (pin "P47") (pinfunction "IO_L48N_RDWR_B_VREF_2_P47") (pintype "bidirectional"))
    )
    (net (code "31") (name "A13'") (class "Default")
      (node (ref "U2") (pin "28") (pinfunction "A13_28") (pintype "input"))
      (node (ref "U3") (pin "44") (pinfunction "PE13_44") (pintype "bidirectional"))
      (node (ref "U6") (pin "P100") (pinfunction "IO_L33P_1_P100") (pintype "bidirectional"))
    )
    (net (code "32") (name "A14") (class "Default")
      (node (ref "12B") (pin "1") (pinfunction "P_1") (pintype "passive"))
      (node (ref "U6") (pin "P45") (pinfunction "IO_L49N_D4_2_P45") (pintype "bidirectional"))
    )
    (net (code "33") (name "A14'") (class "Default")
      (node (ref "U2") (pin "3") (pinfunction "A14_3") (pintype "input"))
      (node (ref "U3") (pin "45") (pinfunction "PE14_45") (pintype "bidirectional"))
      (node (ref "U6") (pin "P111") (pinfunction "IO_L66N_SCP0_0_P111") (pintype "bidirectional"))
    )
    (net (code "34") (name "A15") (class "Default")
      (node (ref "11B") (pin "1") (pinfunction "P_1") (pintype "passive"))
      (node (ref "U6") (pin "P43") (pinfunction "IO_L62N_D6_2_P43") (pintype "bidirectional"))
    )
    (net (code "35") (name "A15'") (class "Default")
      (node (ref "U2") (pin "31") (pinfunction "A15_31") (pintype "input"))
      (node (ref "U3") (pin "46") (pinfunction "PE15_46") (pintype "bidirectional"))
      (node (ref "U6") (pin "P112") (pinfunction "IO_L66P_SCP1_0_P112") (pintype "bidirectional"))
    )
    (net (code "36") (name "A16'") (class "Default")
      (node (ref "U2") (pin "2") (pinfunction "A16_2") (pintype "input"))
      (node (ref "U3") (pin "48") (pinfunction "PB11_48") (pintype "bidirectional"))
      (node (ref "U6") (pin "P114") (pinfunction "IO_L65N_SCP2_0_P114") (pintype "bidirectional"))
    )
    (net (code "37") (name "A17'") (class "Default")
      (node (ref "U2") (pin "30") (pinfunction "A17_30") (pintype "input"))
      (node (ref "U3") (pin "51") (pinfunction "PB12_51") (pintype "bidirectional"))
      (node (ref "U6") (pin "P61") (pinfunction "IO_L12N_D2_MISO3_2_P61") (pintype "bidirectional"))
    )
    (net (code "38") (name "A18'") (class "Default")
      (node (ref "U2") (pin "1") (pinfunction "A18_1") (pintype "input"))
      (node (ref "U3") (pin "52") (pinfunction "PB13_52") (pintype "bidirectional"))
      (node (ref "U6") (pin "P115") (pinfunction "IO_L65P_SCP3_0_P115") (pintype "bidirectional"))
    )
    (net (code "39") (name "B0") (class "Default")
      (node (ref "U3") (pin "55") (pinfunction "PD8_55") (pintype "bidirectional"))
      (node (ref "U6") (pin "P116") (pinfunction "IO_L64N_SCP4_0_P116") (pintype "bidirectional"))
    )
    (net (code "40") (name "B1") (class "Default")
      (node (ref "U3") (pin "56") (pinfunction "PD9_56") (pintype "bidirectional"))
      (node (ref "U6") (pin "P117") (pinfunction "IO_L64P_SCP5_0_P117") (pintype "bidirectional"))
    )
    (net (code "41") (name "B2") (class "Default")
      (node (ref "U3") (pin "57") (pinfunction "PD10_57") (pintype "bidirectional"))
      (node (ref "U6") (pin "P118") (pinfunction "IO_L63N_SCP6_0_P118") (pintype "bidirectional"))
    )
    (net (code "42") (name "B3") (class "Default")
      (node (ref "U3") (pin "58") (pinfunction "PD11_58") (pintype "bidirectional"))
      (node (ref "U6") (pin "P119") (pinfunction "IO_L63P_SCP7_0_P119") (pintype "bidirectional"))
    )
    (net (code "43") (name "B4") (class "Default")
      (node (ref "U3") (pin "59") (pinfunction "PD12_59") (pintype "bidirectional"))
      (node (ref "U6") (pin "P120") (pinfunction "IO_L62N_VREF_0_P120") (pintype "bidirectional"))
    )
    (net (code "44") (name "B5") (class "Default")
      (node (ref "U3") (pin "60") (pinfunction "PD13_60") (pintype "bidirectional"))
      (node (ref "U6") (pin "P121") (pinfunction "IO_L62P_0_P121") (pintype "bidirectional"))
    )
    (net (code "45") (name "B6") (class "Default")
      (node (ref "U3") (pin "61") (pinfunction "PD14_61") (pintype "bidirectional"))
      (node (ref "U6") (pin "P123") (pinfunction "IO_L37N_GCLK12_0_P123") (pintype "bidirectional"))
    )
    (net (code "46") (name "B7") (class "Default")
      (node (ref "U3") (pin "62") (pinfunction "PD15_62") (pintype "bidirectional"))
      (node (ref "U6") (pin "P124") (pinfunction "IO_L37P_GCLK13_0_P124") (pintype "bidirectional"))
    )
    (net (code "47") (name "BOOT0") (class "Default")
      (node (ref "R24") (pin "1") (pinfunction "1_1") (pintype "passive"))
      (node (ref "R30") (pin "2") (pinfunction "2_2") (pintype "passive"))
      (node (ref "U3") (pin "94") (pinfunction "BOOT0_94") (pintype "bidirectional"))
    )
    (net (code "48") (name "BRIGHT") (class "Default")
      (node (ref "R33") (pin "1") (pinfunction "1_1") (pintype "passive"))
      (node (ref "R34") (pin "1") (pinfunction "1_1") (pintype "passive"))
      (node (ref "R35") (pin "1") (pinfunction "1_1") (pintype "passive"))
      (node (ref "U6") (pin "P11") (pinfunction "IO_L49N_3_P11") (pintype "bidirectional"))
    )
    (net (code "49") (name "CC1") (class "Default")
      (node (ref "J3") (pin "A5") (pinfunction "CC1_A5") (pintype "bidirectional"))
    )
    (net (code "50") (name "CC2") (class "Default")
      (node (ref "J3") (pin "B5") (pinfunction "CC2_B5") (pintype "bidirectional"))
    )
    (net (code "51") (name "CFG_CLK") (class "Default")
      (node (ref "U3") (pin "35") (pinfunction "PB0_35") (pintype "bidirectional"))
      (node (ref "U6") (pin "P17") (pinfunction "IO_L43P_GCLK23_3_P17") (pintype "bidirectional"))
    )
    (net (code "52") (name "CFG_DATA") (class "Default")
      (node (ref "U3") (pin "89") (pinfunction "PB3_89") (pintype "bidirectional"))
      (node (ref "U6") (pin "P15") (pinfunction "IO_L44P_GCLK21_3_P15") (pintype "bidirectional"))
    )
    (net (code "53") (name "CFG_RESET") (class "Default")
      (node (ref "U3") (pin "36") (pinfunction "PB1_36") (pintype "bidirectional"))
      (node (ref "U6") (pin "P16") (pinfunction "IO_L43N_GCLK22_IRDY2_3_P16") (pintype "bidirectional"))
    )
    (net (code "54") (name "COMPOSITE") (class "Default")
      (node (ref "R4") (pin "1") (pinfunction "1_1") (pintype "passive"))
      (node (ref "X1") (pin "19") (pinfunction "19_19") (pintype "passive"))
      (node (ref "X2") (pin "2") (pinfunction "1_2") (pintype "passive"))
    )
    (net (code "55") (name "CSYNC") (class "Default")
      (node (ref "SJ1") (pin "1") (pinfunction "1_1") (pintype "passive"))
      (node (ref "U1") (pin "16") (pinfunction "HSYNC_16") (pintype "input"))
      (node (ref "U6") (pin "P10") (pinfunction "IO_L50P_3_P10") (pintype "bidirectional"))
    )
    (net (code "56") (name "CS_LLS") (class "Default")
      (node (ref "MICRO_SD1") (pin "2") (pinfunction "CD/DAT3_2") (pintype "bidirectional"))
      (node (ref "R21") (pin "2") (pinfunction "2_2") (pintype "passive"))
    )
    (net (code "57") (name "CTRL_CLK") (class "Default")
      (node (ref "U3") (pin "90") (pinfunction "PB4_90") (pintype "bidirectional"))
      (node (ref "U6") (pin "P6") (pinfunction "IO_L52P_3_P6") (pintype "bidirectional"))
    )
    (net (code "58") (name "D0") (class "Default")
      (node (ref "4A") (pin "1") (pinfunction "P_1") (pintype "passive"))
      (node (ref "U2") (pin "13") (pinfunction "DQ0_13") (pintype "output"))
      (node (ref "U6") (pin "P23") (pinfunction "IO_L41N_GCLK26_3_P23") (pintype "bidirectional"))
    )
    (net (code "59") (name "D1") (class "Default")
      (node (ref "5A") (pin "1") (pinfunction "P_1") (pintype "passive"))
      (node (ref "U2") (pin "14") (pinfunction "DQ1_14") (pintype "output"))
      (node (ref "U6") (pin "P26") (pinfunction "IO_L37N_3_P26") (pintype "bidirectional"))
    )
    (net (code "60") (name "D2") (class "Default")
      (node (ref "6A") (pin "1") (pinfunction "P_1") (pintype "passive"))
      (node (ref "U2") (pin "15") (pinfunction "DQ2_15") (pintype "output"))
      (node (ref "U6") (pin "P27") (pinfunction "IO_L37P_3_P27") (pintype "bidirectional"))
    )
    (net (code "61") (name "D3") (class "Default")
      (node (ref "9A") (pin "1") (pinfunction "P_1") (pintype "passive"))
      (node (ref "U2") (pin "17") (pinfunction "DQ3_17") (pintype "output"))
      (node (ref "U6") (pin "P34") (pinfunction "IO_L1N_VREF_3_P34") (pintype "bidirectional"))
    )
    (net (code "62") (name "D4") (class "Default")
      (node (ref "10A") (pin "1") (pinfunction "P_1") (pintype "passive"))
      (node (ref "U2") (pin "18") (pinfunction "DQ4_18") (pintype "output"))
      (node (ref "U6") (pin "P39") (pinfunction "IO_L65P_INIT_B_2_P39") (pintype "bidirectional"))
    )
    (net (code "63") (name "D5") (class "Default")
      (node (ref "8A") (pin "1") (pinfunction "P_1") (pintype "passive"))
      (node (ref "U2") (pin "19") (pinfunction "DQ5_19") (pintype "output"))
      (node (ref "U6") (pin "P32") (pinfunction "IO_L2N_3_P32") (pintype "bidirectional"))
    )
    (net (code "64") (name "D6") (class "Default")
      (node (ref "7A") (pin "1") (pinfunction "P_1") (pintype "passive"))
      (node (ref "U2") (pin "20") (pinfunction "DQ6_20") (pintype "output"))
      (node (ref "U6") (pin "P29") (pinfunction "IO_L36N_3_P29") (pintype "bidirectional"))
    )
    (net (code "65") (name "D7") (class "Default")
      (node (ref "1A") (pin "1") (pinfunction "P_1") (pintype "passive"))
      (node (ref "U2") (pin "21") (pinfunction "DQ7_21") (pintype "output"))
      (node (ref "U6") (pin "P21") (pinfunction "IO_L42N_GCLK24_3_P21") (pintype "bidirectional"))
    )
    (net (code "66") (name "DI_LLS") (class "Default")
      (node (ref "MICRO_SD1") (pin "3") (pinfunction "CMD_3") (pintype "bidirectional"))
      (node (ref "R17") (pin "2") (pinfunction "2_2") (pintype "passive"))
    )
    (net (code "67") (name "DOWN") (class "Default")
      (node (ref "J2") (pin "2") (pinfunction "2_2") (pintype "passive"))
      (node (ref "U6") (pin "P79") (pinfunction "IO_L47P_1_P79") (pintype "bidirectional"))
    )
    (net (code "68") (name "EN_M1_NOT") (class "Default")
      (node (ref "U3") (pin "25") (pinfunction "PA2_25") (pintype "bidirectional"))
      (node (ref "U6") (pin "P140") (pinfunction "IO_L3P_0_P140") (pintype "bidirectional"))
    )
    (net (code "69") (name "FIRE") (class "Default")
      (node (ref "J2") (pin "6") (pinfunction "6_6") (pintype "passive"))
      (node (ref "U6") (pin "P82") (pinfunction "IO_L45N_1_P82") (pintype "bidirectional"))
    )
    (net (code "70") (name "FLASH_CS") (class "Default")
      (node (ref "U4") (pin "1") (pinfunction "CS_1") (pintype "bidirectional"))
      (node (ref "U6") (pin "P38") (pinfunction "IO_L65N_CSO_B_2_P38") (pintype "bidirectional"))
    )
    (net (code "71") (name "FLASH_MISO") (class "Default")
      (node (ref "U4") (pin "2") (pinfunction "MISO_2") (pintype "bidirectional"))
      (node (ref "U6") (pin "P65") (pinfunction "IO_L3P_D0_DIN_MISO_MISO1_2_P65") (pintype "bidirectional"))
    )
    (net (code "72") (name "FLASH_MOSI") (class "Default")
      (node (ref "U4") (pin "5") (pinfunction "MOSI_5") (pintype "bidirectional"))
      (node (ref "U6") (pin "P64") (pinfunction "IO_L3N_MOSI_CSI_B_MISO0_2_P64") (pintype "bidirectional"))
    )
    (net (code "73") (name "FLASH_SCLK") (class "Default")
      (node (ref "U4") (pin "6") (pinfunction "SCK_6") (pintype "bidirectional"))
      (node (ref "U6") (pin "P70") (pinfunction "IO_L1P_CCLK_2_P70") (pintype "bidirectional"))
    )
    (net (code "74") (name "GET_CTRL_REG") (class "Default")
      (node (ref "U3") (pin "66") (pinfunction "PC9_66") (pintype "bidirectional"))
      (node (ref "U6") (pin "P5") (pinfunction "IO_L52N_3_P5") (pintype "bidirectional"))
    )
    (net (code "75") (name "GET_DATA_REG") (class "Default")
      (node (ref "U3") (pin "78") (pinfunction "PC10_78") (pintype "bidirectional"))
      (node (ref "U6") (pin "P2") (pinfunction "IO_L83P_3_P2") (pintype "bidirectional"))
    )
    (net (code "76") (name "GND") (class "Default")
      (node (ref "4B") (pin "1") (pinfunction "P_1") (pintype "passive"))
      (node (ref "5B") (pin "1") (pinfunction "P_1") (pintype "passive"))
      (node (ref "BT1") (pin "N") (pinfunction "NEG_N") (pintype "passive"))
      (node (ref "C10") (pin "2") (pinfunction "2_2") (pintype "passive"))
      (node (ref "C11") (pin "1") (pinfunction "1_1") (pintype "passive"))
      (node (ref "C12") (pin "1") (pinfunction "1_1") (pintype "passive"))
      (node (ref "C18") (pin "2") (pinfunction "2_2") (pintype "passive"))
      (node (ref "C19") (pin "2") (pinfunction "2_2") (pintype "passive"))
      (node (ref "C2") (pin "2") (pinfunction "2_2") (pintype "passive"))
      (node (ref "C22") (pin "1") (pinfunction "1_1") (pintype "passive"))
      (node (ref "C23") (pin "1") (pinfunction "1_1") (pintype "passive"))
      (node (ref "C24") (pin "2") (pinfunction "2_2") (pintype "passive"))
      (node (ref "C25") (pin "2") (pinfunction "2_2") (pintype "passive"))
      (node (ref "C26") (pin "2") (pinfunction "2_2") (pintype "passive"))
      (node (ref "C3") (pin "2") (pinfunction "2_2") (pintype "passive"))
      (node (ref "C33") (pin "2") (pinfunction "2_2") (pintype "passive"))
      (node (ref "C4") (pin "1") (pinfunction "1_1") (pintype "passive"))
      (node (ref "C5") (pin "1") (pinfunction "1_1") (pintype "passive"))
      (node (ref "C6") (pin "2") (pinfunction "2_2") (pintype "passive"))
      (node (ref "C7") (pin "2") (pinfunction "2_2") (pintype "passive"))
      (node (ref "C8") (pin "1") (pinfunction "1_1") (pintype "passive"))
      (node (ref "C9") (pin "1") (pinfunction "1_1") (pintype "passive"))
      (node (ref "IC2") (pin "1") (pinfunction "GND_1") (pintype "power_in"))
      (node (ref "IC5") (pin "1") (pinfunction "GND_1") (pintype "power_in"))
      (node (ref "J2") (pin "8") (pinfunction "8_8") (pintype "passive"))
      (node (ref "J3") (pin "A1_B12") (pinfunction "GND_A1_B12") (pintype "power_in"))
      (node (ref "J3") (pin "B1_A12") (pinfunction "GND_B1_A12") (pintype "power_in"))
      (node (ref "J3") (pin "SH1") (pinfunction "SHIELD_SH1") (pintype "passive"))
      (node (ref "J3") (pin "SH2") (pinfunction "SHIELD_SH2") (pintype "passive"))
      (node (ref "J3") (pin "SH3") (pinfunction "SHIELD_SH3") (pintype "passive"))
      (node (ref "J3") (pin "SH4") (pinfunction "SHIELD_SH4") (pintype "passive"))
      (node (ref "J4") (pin "1") (pinfunction "1_1") (pintype "passive"))
      (node (ref "JP4") (pin "2") (pinfunction "2_2") (pintype "passive"))
      (node (ref "JP5") (pin "2") (pinfunction "2_2") (pintype "passive"))
      (node (ref "JP6") (pin "2") (pinfunction "2_2") (pintype "passive"))
      (node (ref "JP8") (pin "2") (pinfunction "2_2") (pintype "passive"))
      (node (ref "LED3") (pin "P1") (pinfunction "C_P1") (pintype "passive"))
      (node (ref "LED3") (pin "P2") (pinfunction "C_P2") (pintype "passive"))
      (node (ref "LED3") (pin "P3") (pinfunction "C_P3") (pintype "passive"))
      (node (ref "MICRO_SD1") (pin "6") (pinfunction "VSS_6") (pintype "power_in"))
      (node (ref "MICRO_SD1") (pin "MP1") (pinfunction "SHIELD_MP1") (pintype "power_in"))
      (node (ref "MICRO_SD1") (pin "MP2") (pinfunction "SHIELD_MP2") (pintype "power_in"))
      (node (ref "MICRO_SD1") (pin "MP3") (pinfunction "SHIELD_MP3") (pintype "power_in"))
      (node (ref "MICRO_SD1") (pin "MP4") (pinfunction "SHIELD_MP4") (pintype "power_in"))
      (node (ref "R19") (pin "2") (pinfunction "2_2") (pintype "passive"))
      (node (ref "R25") (pin "1") (pinfunction "1_1") (pintype "passive"))
      (node (ref "R27") (pin "2") (pinfunction "2_2") (pintype "passive"))
      (node (ref "R28") (pin "2") (pinfunction "2_2") (pintype "passive"))
      (node (ref "R30") (pin "1") (pinfunction "1_1") (pintype "passive"))
      (node (ref "R37") (pin "2") (pinfunction "2_2") (pintype "passive"))
      (node (ref "S1") (pin "1") (pinfunction "P_1") (pintype "passive"))
      (node (ref "U1") (pin "12") (pinfunction "SELECT_12") (pintype "input"))
      (node (ref "U1") (pin "13") (pinfunction "DGND_13") (pintype "passive"))
      (node (ref "U1") (pin "2") (pinfunction "AGND_2") (pintype "passive"))
      (node (ref "U2") (pin "16") (pinfunction "VSS_16") (pintype "output"))
      (node (ref "U2") (pin "22") (pinfunction "CE_22") (pintype "input"))
      (node (ref "U3") (pin "10") (pinfunction "VSS_10") (pintype "bidirectional"))
      (node (ref "U3") (pin "20") (pinfunction "VSSA_20") (pintype "bidirectional"))
      (node (ref "U3") (pin "27") (pinfunction "VSS_27") (pintype "bidirectional"))
      (node (ref "U3") (pin "74") (pinfunction "VSS_74") (pintype "bidirectional"))
      (node (ref "U3") (pin "99") (pinfunction "VSS_99") (pintype "bidirectional"))
      (node (ref "U4") (pin "4") (pinfunction "GND_4") (pintype "power_in"))
      (node (ref "U5") (pin "7") (pinfunction "GND_7") (pintype "power_in"))
      (node (ref "U6") (pin "P108") (pinfunction "GND_P108") (pintype "bidirectional"))
      (node (ref "U6") (pin "P113") (pinfunction "GND_P113") (pintype "bidirectional"))
      (node (ref "U6") (pin "P13") (pinfunction "GND_P13") (pintype "bidirectional"))
      (node (ref "U6") (pin "P130") (pinfunction "GND_P130") (pintype "bidirectional"))
      (node (ref "U6") (pin "P136") (pinfunction "GND_P136") (pintype "bidirectional"))
      (node (ref "U6") (pin "P25") (pinfunction "GND_P25") (pintype "bidirectional"))
      (node (ref "U6") (pin "P3") (pinfunction "GND_P3") (pintype "bidirectional"))
      (node (ref "U6") (pin "P49") (pinfunction "GND_P49") (pintype "bidirectional"))
      (node (ref "U6") (pin "P54") (pinfunction "GND_P54") (pintype "bidirectional"))
      (node (ref "U6") (pin "P68") (pinfunction "GND_P68") (pintype "bidirectional"))
      (node (ref "U6") (pin "P73") (pinfunction "SUSPEND_P73") (pintype "bidirectional"))
      (node (ref "U6") (pin "P77") (pinfunction "GND_P77") (pintype "bidirectional"))
      (node (ref "U6") (pin "P91") (pinfunction "GND_P91") (pintype "bidirectional"))
      (node (ref "U6") (pin "P96") (pinfunction "GND_P96") (pintype "bidirectional"))
      (node (ref "X1") (pin "13") (pinfunction "13_13") (pintype "passive"))
      (node (ref "X1") (pin "14") (pinfunction "14_14") (pintype "passive"))
      (node (ref "X1") (pin "17") (pinfunction "17_17") (pintype "passive"))
      (node (ref "X1") (pin "18") (pinfunction "18_18") (pintype "passive"))
      (node (ref "X1") (pin "21") (pinfunction "21_21") (pintype "passive"))
      (node (ref "X1") (pin "4") (pinfunction "4_4") (pintype "passive"))
      (node (ref "X1") (pin "5") (pinfunction "5_5") (pintype "passive"))
      (node (ref "X1") (pin "8") (pinfunction "8_8") (pintype "passive"))
      (node (ref "X1") (pin "9") (pinfunction "9_9") (pintype "passive"))
      (node (ref "X2") (pin "1") (pinfunction "2_1") (pintype "passive"))
    )
    (net (code "77") (name "LEDB") (class "Default")
      (node (ref "R3") (pin "1") (pinfunction "1_1") (pintype "passive"))
      (node (ref "U3") (pin "64") (pinfunction "PC7_64") (pintype "bidirectional"))
    )
    (net (code "78") (name "LEDG") (class "Default")
      (node (ref "R13") (pin "1") (pinfunction "1_1") (pintype "passive"))
      (node (ref "U3") (pin "63") (pinfunction "PC6_63") (pintype "bidirectional"))
    )
    (net (code "79") (name "LEDR") (class "Default")
      (node (ref "R2") (pin "1") (pinfunction "1_1") (pintype "passive"))
      (node (ref "U3") (pin "65") (pinfunction "PC8_65") (pintype "bidirectional"))
    )
    (net (code "80") (name "LEFT") (class "Default")
      (node (ref "J2") (pin "3") (pinfunction "3_3") (pintype "passive"))
      (node (ref "U6") (pin "P80") (pinfunction "IO_L46N_1_P80") (pintype "bidirectional"))
    )
    (net (code "81") (name "LE_IL") (class "Default")
      (node (ref "U3") (pin "7") (pinfunction "PC13_7") (pintype "bidirectional"))
      (node (ref "U6") (pin "P14") (pinfunction "IO_L44N_GCLK20_3_P14") (pintype "bidirectional"))
    )
    (net (code "82") (name "MISO") (class "Default")
      (node (ref "R20") (pin "1") (pinfunction "1_1") (pintype "passive"))
      (node (ref "U3") (pin "31") (pinfunction "PA6_31") (pintype "bidirectional"))
    )
    (net (code "83") (name "MOSI") (class "Default")
      (node (ref "R17") (pin "1") (pinfunction "1_1") (pintype "passive"))
      (node (ref "U3") (pin "32") (pinfunction "PA7_32") (pintype "bidirectional"))
    )
    (net (code "84") (name "Net-(1B-P)") (class "Default")
      (node (ref "1B") (pin "1") (pinfunction "P_1") (pintype "passive"))
      (node (ref "D4") (pin "A") (pinfunction "A_A") (pintype "passive"))
    )
    (net (code "85") (name "Net-(BT1-POS)") (class "Default")
      (node (ref "BT1") (pin "P") (pinfunction "POS_P") (pintype "passive"))
      (node (ref "D3") (pin "2") (pinfunction "A2_2") (pintype "passive"))
      (node (ref "U3") (pin "16") (pinfunction "PC1_16") (pintype "bidirectional"))
    )
    (net (code "86") (name "Net-(C1-Pad-)") (class "Default")
      (node (ref "C1") (pin "-") (pinfunction "-_-") (pintype "passive"))
      (node (ref "R4") (pin "2") (pinfunction "2_2") (pintype "passive"))
    )
    (net (code "87") (name "Net-(C9-Pad2)") (class "Default")
      (node (ref "C9") (pin "2") (pinfunction "2_2") (pintype "passive"))
      (node (ref "R5") (pin "2") (pinfunction "2_2") (pintype "passive"))
    )
    (net (code "88") (name "Net-(C13-Pad1)") (class "Default")
      (node (ref "C13") (pin "1") (pinfunction "1_1") (pintype "passive"))
      (node (ref "J4") (pin "4") (pinfunction "4_4") (pintype "passive"))
      (node (ref "J4") (pin "5") (pinfunction "5_5") (pintype "passive"))
    )
    (net (code "89") (name "Net-(C13-Pad2)") (class "Default")
      (node (ref "C13") (pin "2") (pinfunction "2_2") (pintype "passive"))
      (node (ref "R6") (pin "2") (pinfunction "2_2") (pintype "passive"))
    )
    (net (code "90") (name "Net-(C14-Pad-)") (class "Default")
      (node (ref "C14") (pin "-") (pinfunction "-_-") (pintype "passive"))
      (node (ref "JP1") (pin "2") (pinfunction "2_2") (pintype "passive"))
    )
    (net (code "91") (name "Net-(D3-CC)") (class "Default")
      (node (ref "D3") (pin "3") (pinfunction "CC_3") (pintype "passive"))
      (node (ref "U3") (pin "6") (pinfunction "VBAT_6") (pintype "bidirectional"))
    )
    (net (code "92") (name "Net-(J3-DN1)") (class "Default")
      (node (ref "J3") (pin "A7") (pinfunction "DN1_A7") (pintype "bidirectional"))
      (node (ref "J3") (pin "B7") (pinfunction "DN2_B7") (pintype "bidirectional"))
      (node (ref "R26") (pin "1") (pinfunction "1_1") (pintype "passive"))
    )
    (net (code "93") (name "Net-(J3-DP1)") (class "Default")
      (node (ref "J3") (pin "A6") (pinfunction "DP1_A6") (pintype "bidirectional"))
      (node (ref "J3") (pin "B6") (pinfunction "DP2_B6") (pintype "bidirectional"))
      (node (ref "R22") (pin "1") (pinfunction "1_1") (pintype "passive"))
      (node (ref "R23") (pin "1") (pinfunction "1_1") (pintype "passive"))
    )
    (net (code "94") (name "Net-(JP2-Pad1)") (class "Default")
      (node (ref "JP2") (pin "1") (pinfunction "1_1") (pintype "passive"))
      (node (ref "X1") (pin "16") (pinfunction "16_16") (pintype "passive"))
    )
    (net (code "95") (name "Net-(JP2-Pad2)") (class "Default")
      (node (ref "JP2") (pin "2") (pinfunction "2_2") (pintype "passive"))
      (node (ref "R36") (pin "1") (pinfunction "1_1") (pintype "passive"))
    )
    (net (code "96") (name "Net-(JP7-Pad1)") (class "Default")
      (node (ref "JP7") (pin "1") (pinfunction "1_1") (pintype "passive"))
      (node (ref "R24") (pin "2") (pinfunction "2_2") (pintype "passive"))
    )
    (net (code "97") (name "Net-(JP7-Pad3)") (class "Default")
      (node (ref "JP7") (pin "3") (pinfunction "3_3") (pintype "passive"))
      (node (ref "R16") (pin "1") (pinfunction "1_1") (pintype "passive"))
    )
    (net (code "98") (name "Net-(LED2-PadA)") (class "Default")
      (node (ref "LED2") (pin "A") (pinfunction "A_A") (pintype "passive"))
      (node (ref "R11") (pin "2") (pinfunction "2_2") (pintype "passive"))
    )
    (net (code "99") (name "Net-(LED3A-A)") (class "Default")
      (node (ref "LED3") (pin "P6") (pinfunction "A_P6") (pintype "passive"))
      (node (ref "R3") (pin "2") (pinfunction "2_2") (pintype "passive"))
    )
    (net (code "100") (name "Net-(LED3B-A)") (class "Default")
      (node (ref "LED3") (pin "P5") (pinfunction "A_P5") (pintype "passive"))
      (node (ref "R13") (pin "2") (pinfunction "2_2") (pintype "passive"))
    )
    (net (code "101") (name "Net-(LED3C-A)") (class "Default")
      (node (ref "LED3") (pin "P4") (pinfunction "A_P4") (pintype "passive"))
      (node (ref "R2") (pin "2") (pinfunction "2_2") (pintype "passive"))
    )
    (net (code "102") (name "Net-(MICRO_SD1-DAT0)") (class "Default")
      (node (ref "MICRO_SD1") (pin "7") (pinfunction "DAT0_7") (pintype "bidirectional"))
      (node (ref "R20") (pin "2") (pinfunction "2_2") (pintype "passive"))
    )
    (net (code "103") (name "Net-(Q3-2)") (class "Default")
      (node (ref "C12") (pin "2") (pinfunction "2_2") (pintype "passive"))
      (node (ref "Q3") (pin "3") (pinfunction "2_3") (pintype "passive"))
      (node (ref "R14") (pin "2") (pinfunction "2_2") (pintype "passive"))
      (node (ref "U3") (pin "13") (pinfunction "PH1_13") (pintype "bidirectional"))
    )
    (net (code "104") (name "Net-(R10-Pad2)") (class "Default")
      (node (ref "R10") (pin "2") (pinfunction "2_2") (pintype "passive"))
      (node (ref "R32") (pin "2") (pinfunction "2_2") (pintype "passive"))
      (node (ref "R35") (pin "2") (pinfunction "2_2") (pintype "passive"))
    )
    (net (code "105") (name "Net-(R29-Pad2)") (class "Default")
      (node (ref "R29") (pin "2") (pinfunction "2_2") (pintype "passive"))
      (node (ref "R33") (pin "2") (pinfunction "2_2") (pintype "passive"))
      (node (ref "R8") (pin "2") (pinfunction "2_2") (pintype "passive"))
    )
    (net (code "106") (name "Net-(R31-Pad2)") (class "Default")
      (node (ref "R31") (pin "2") (pinfunction "2_2") (pintype "passive"))
      (node (ref "R34") (pin "2") (pinfunction "2_2") (pintype "passive"))
      (node (ref "R9") (pin "2") (pinfunction "2_2") (pintype "passive"))
    )
    (net (code "107") (name "Net-(U1-COMP)") (class "Default")
      (node (ref "C1") (pin "+") (pinfunction "+_+") (pintype "passive"))
      (node (ref "SJ1") (pin "2") (pinfunction "2_2") (pintype "passive"))
      (node (ref "U1") (pin "10") (pinfunction "COMP_10") (pintype "output"))
    )
    (net (code "108") (name "Net-(U3-PC14)") (class "Default")
      (node (ref "C22") (pin "2") (pinfunction "2_2") (pintype "passive"))
      (node (ref "Q4") (pin "2") (pinfunction "2_2") (pintype "passive"))
      (node (ref "U3") (pin "8") (pinfunction "PC14_8") (pintype "bidirectional"))
    )
    (net (code "109") (name "Net-(U3-PC15)") (class "Default")
      (node (ref "C23") (pin "2") (pinfunction "2_2") (pintype "passive"))
      (node (ref "Q4") (pin "1") (pinfunction "1_1") (pintype "passive"))
      (node (ref "U3") (pin "9") (pinfunction "PC15_9") (pintype "bidirectional"))
    )
    (net (code "110") (name "Net-(U3-PH0)") (class "Default")
      (node (ref "C11") (pin "2") (pinfunction "2_2") (pintype "passive"))
      (node (ref "Q3") (pin "1") (pinfunction "1_1") (pintype "passive"))
      (node (ref "R14") (pin "1") (pinfunction "1_1") (pintype "passive"))
      (node (ref "U3") (pin "12") (pinfunction "PH0_12") (pintype "bidirectional"))
    )
    (net (code "111") (name "Net-(U3-VCAP_1)") (class "Default")
      (node (ref "C10") (pin "1") (pinfunction "1_1") (pintype "passive"))
      (node (ref "U3") (pin "49") (pinfunction "VCAP_1_49") (pintype "bidirectional"))
    )
    (net (code "112") (name "Net-(U3-VCAP_2)") (class "Default")
      (node (ref "C7") (pin "1") (pinfunction "1_1") (pintype "passive"))
      (node (ref "U3") (pin "73") (pinfunction "VCAP_2_73") (pintype "bidirectional"))
    )
    (net (code "113") (name "Net-(U5-IN+)") (class "Default")
      (node (ref "R6") (pin "1") (pinfunction "1_1") (pintype "passive"))
      (node (ref "U5") (pin "3") (pinfunction "IN+_3") (pintype "input"))
    )
    (net (code "114") (name "Net-(U5-IN-)") (class "Default")
      (node (ref "R5") (pin "1") (pinfunction "1_1") (pintype "passive"))
      (node (ref "U5") (pin "4") (pinfunction "IN-_4") (pintype "input"))
    )
    (net (code "115") (name "Net-(U5-VO+)") (class "Default")
      (node (ref "C14") (pin "+") (pinfunction "+_+") (pintype "passive"))
      (node (ref "U5") (pin "5") (pinfunction "VO+_5") (pintype "output"))
    )
    (net (code "116") (name "Net-(U5-VO-)") (class "Default")
      (node (ref "JP1") (pin "1") (pinfunction "1_1") (pintype "passive"))
      (node (ref "U5") (pin "8") (pinfunction "VO-_8") (pintype "output"))
    )
    (net (code "117") (name "Net-(U5-~{SD})") (class "Default")
      (node (ref "R7") (pin "1") (pinfunction "1_1") (pintype "passive"))
      (node (ref "U5") (pin "1") (pinfunction "~{SD}_1") (pintype "input"))
    )
    (net (code "118") (name "Net-(U6-PROGRAM_B_2)") (class "Default")
      (node (ref "R12") (pin "2") (pinfunction "2_2") (pintype "passive"))
      (node (ref "U6") (pin "P37") (pinfunction "PROGRAM_B_2_P37") (pintype "bidirectional"))
    )
    (net (code "119") (name "O0") (class "Default")
      (node (ref "U3") (pin "81") (pinfunction "PD0_81") (pintype "bidirectional"))
      (node (ref "U6") (pin "P126") (pinfunction "IO_L36N_GCLK14_0_P126") (pintype "bidirectional"))
    )
    (net (code "120") (name "O1") (class "Default")
      (node (ref "U3") (pin "82") (pinfunction "PD1_82") (pintype "bidirectional"))
      (node (ref "U6") (pin "P127") (pinfunction "IO_L36P_GCLK15_0_P127") (pintype "bidirectional"))
    )
    (net (code "121") (name "O2") (class "Default")
      (node (ref "U3") (pin "83") (pinfunction "PD2_83") (pintype "bidirectional"))
      (node (ref "U6") (pin "P131") (pinfunction "IO_L35N_GCLK16_0_P131") (pintype "bidirectional"))
    )
    (net (code "122") (name "O3") (class "Default")
      (node (ref "U3") (pin "84") (pinfunction "PD3_84") (pintype "bidirectional"))
      (node (ref "U6") (pin "P132") (pinfunction "IO_L35P_GCLK17_0_P132") (pintype "bidirectional"))
    )
    (net (code "123") (name "O4") (class "Default")
      (node (ref "U3") (pin "85") (pinfunction "PD4_85") (pintype "bidirectional"))
      (node (ref "U6") (pin "P133") (pinfunction "IO_L34N_GCLK18_0_P133") (pintype "bidirectional"))
    )
    (net (code "124") (name "O5") (class "Default")
      (node (ref "U3") (pin "86") (pinfunction "PD5_86") (pintype "bidirectional"))
      (node (ref "U6") (pin "P134") (pinfunction "IO_L34P_GCLK19_0_P134") (pintype "bidirectional"))
    )
    (net (code "125") (name "O6") (class "Default")
      (node (ref "U3") (pin "87") (pinfunction "PD6_87") (pintype "bidirectional"))
      (node (ref "U6") (pin "P137") (pinfunction "IO_L4N_0_P137") (pintype "bidirectional"))
    )
    (net (code "126") (name "O7") (class "Default")
      (node (ref "U3") (pin "88") (pinfunction "PD7_88") (pintype "bidirectional"))
      (node (ref "U6") (pin "P138") (pinfunction "IO_L4P_0_P138") (pintype "bidirectional"))
    )
    (net (code "127") (name "PA11{slash}USB_DN") (class "Default")
      (node (ref "R26") (pin "2") (pinfunction "2_2") (pintype "passive"))
      (node (ref "U3") (pin "70") (pinfunction "PA11_70") (pintype "bidirectional"))
    )
    (net (code "128") (name "PA12{slash}USB_DP") (class "Default")
      (node (ref "R23") (pin "2") (pinfunction "2_2") (pintype "passive"))
      (node (ref "U3") (pin "71") (pinfunction "PA12_71") (pintype "bidirectional"))
    )
    (net (code "129") (name "PA13{slash}JTMS{slash}SWDIO") (class "Default")
      (node (ref "JP8") (pin "1") (pinfunction "1_1") (pintype "passive"))
      (node (ref "U3") (pin "72") (pinfunction "PA13_72") (pintype "bidirectional"))
    )
    (net (code "130") (name "PA14{slash}JTCK{slash}SWCLK") (class "Default")
      (node (ref "JP8") (pin "3") (pinfunction "3_3") (pintype "passive"))
      (node (ref "U3") (pin "76") (pinfunction "PA14_76") (pintype "bidirectional"))
    )
    (net (code "131") (name "PAGE_A8") (class "Default")
      (node (ref "U3") (pin "24") (pinfunction "PA1_24") (pintype "bidirectional"))
      (node (ref "U6") (pin "P143") (pinfunction "IO_L1N_VREF_0_P143") (pintype "bidirectional"))
    )
    (net (code "132") (name "PAL-NTSC") (class "Default")
      (node (ref "U1") (pin "1") (pinfunction "STND_1") (pintype "input"))
      (node (ref "U6") (pin "P22") (pinfunction "IO_L42P_GCLK25_TRDY2_3_P22") (pintype "bidirectional"))
    )
    (net (code "133") (name "PB2{slash}BOOT1") (class "Default")
      (node (ref "R16") (pin "2") (pinfunction "2_2") (pintype "passive"))
      (node (ref "R25") (pin "2") (pinfunction "2_2") (pintype "passive"))
      (node (ref "U3") (pin "37") (pinfunction "PB2_37") (pintype "bidirectional"))
    )
    (net (code "134") (name "PS2_CLOCK") (class "Default")
      (node (ref "JP6") (pin "3") (pinfunction "3_3") (pintype "passive"))
      (node (ref "U3") (pin "80") (pinfunction "PC12_80") (pintype "bidirectional"))
    )
    (net (code "135") (name "PS2_DATA") (class "Default")
      (node (ref "JP6") (pin "4") (pinfunction "4_4") (pintype "passive"))
      (node (ref "U3") (pin "79") (pinfunction "PC11_79") (pintype "bidirectional"))
    )
    (net (code "136") (name "RESET") (class "Default")
      (node (ref "C5") (pin "2") (pinfunction "2_2") (pintype "passive"))
      (node (ref "D1") (pin "A") (pinfunction "A_A") (pintype "passive"))
      (node (ref "R15") (pin "1") (pinfunction "1_1") (pintype "passive"))
      (node (ref "S1") (pin "2") (pinfunction "S_2") (pintype "passive"))
      (node (ref "U3") (pin "14") (pinfunction "NRST_14") (pintype "bidirectional"))
    )
    (net (code "137") (name "RIGHT") (class "Default")
      (node (ref "J2") (pin "4") (pinfunction "4_4") (pintype "passive"))
      (node (ref "U6") (pin "P81") (pinfunction "IO_L46P_1_P81") (pintype "bidirectional"))
    )
    (net (code "138") (name "ROM_WR_EN") (class "Default")
      (node (ref "U3") (pin "67") (pinfunction "PA8_67") (pintype "bidirectional"))
      (node (ref "U6") (pin "P142") (pinfunction "IO_L2P_0_P142") (pintype "bidirectional"))
    )
    (net (code "139") (name "RST_CTRL_REG") (class "Default")
      (node (ref "U3") (pin "53") (pinfunction "PB14_53") (pintype "bidirectional"))
      (node (ref "U6") (pin "P1") (pinfunction "IO_L83N_VREF_3_P1") (pintype "bidirectional"))
    )
    (net (code "140") (name "RST_DATA_REG") (class "Default")
      (node (ref "U3") (pin "91") (pinfunction "PB5_91") (pintype "bidirectional"))
      (node (ref "U6") (pin "P144") (pinfunction "IO_L1P_HSWAPEN_0_P144") (pintype "bidirectional"))
    )
    (net (code "141") (name "SCK_LLS") (class "Default")
      (node (ref "MICRO_SD1") (pin "5") (pinfunction "CLK_5") (pintype "bidirectional"))
      (node (ref "R18") (pin "2") (pinfunction "2_2") (pintype "passive"))
    )
    (net (code "142") (name "SCL") (class "Default")
      (node (ref "U3") (pin "92") (pinfunction "PB6_92") (pintype "bidirectional"))
    )
    (net (code "143") (name "SCLK") (class "Default")
      (node (ref "R18") (pin "1") (pinfunction "1_1") (pintype "passive"))
      (node (ref "U3") (pin "30") (pinfunction "PA5_30") (pintype "bidirectional"))
    )
    (net (code "144") (name "SDA") (class "Default")
      (node (ref "U3") (pin "93") (pinfunction "PB7_93") (pintype "bidirectional"))
    )
    (net (code "145") (name "SD_LED") (class "Default")
      (node (ref "LED2") (pin "C") (pinfunction "C_C") (pintype "passive"))
      (node (ref "U3") (pin "15") (pinfunction "PC0_15") (pintype "bidirectional"))
    )
    (net (code "146") (name "SEL_128CHARS") (class "Default")
      (node (ref "U3") (pin "77") (pinfunction "PA15_77") (pintype "bidirectional"))
      (node (ref "U6") (pin "P141") (pinfunction "IO_L2N_0_P141") (pintype "bidirectional"))
    )
    (net (code "147") (name "SOUND") (class "Default")
      (node (ref "R1") (pin "2") (pinfunction "2_2") (pintype "passive"))
      (node (ref "U3") (pin "29") (pinfunction "PA4_29") (pintype "bidirectional"))
    )
    (net (code "148") (name "SOUND'") (class "Default")
      (node (ref "J4") (pin "2") (pinfunction "2_2") (pintype "passive"))
      (node (ref "J4") (pin "3") (pinfunction "3_3") (pintype "passive"))
      (node (ref "R1") (pin "1") (pinfunction "1_1") (pintype "passive"))
      (node (ref "R37") (pin "1") (pinfunction "1_1") (pintype "passive"))
      (node (ref "X1") (pin "1") (pinfunction "1_1") (pintype "passive"))
      (node (ref "X1") (pin "3") (pinfunction "3_3") (pintype "passive"))
    )
    (net (code "149") (name "SPARE") (class "Default")
      (node (ref "U6") (pin "P75") (pinfunction "IO_L74P_AWAKE_1_P75") (pintype "bidirectional"))
    )
    (net (code "150") (name "SS_SD") (class "Default")
      (node (ref "R21") (pin "1") (pinfunction "1_1") (pintype "passive"))
      (node (ref "U3") (pin "54") (pinfunction "PB15_54") (pintype "bidirectional"))
    )
    (net (code "151") (name "TCK") (class "Default")
      (node (ref "JP3") (pin "1") (pinfunction "1_1") (pintype "passive"))
      (node (ref "U6") (pin "P109") (pinfunction "TCK_P109") (pintype "bidirectional"))
    )
    (net (code "152") (name "TDI") (class "Default")
      (node (ref "JP3") (pin "3") (pinfunction "3_3") (pintype "passive"))
      (node (ref "U6") (pin "P110") (pinfunction "TDI_P110") (pintype "bidirectional"))
    )
    (net (code "153") (name "TDO") (class "Default")
      (node (ref "JP3") (pin "2") (pinfunction "2_2") (pintype "passive"))
      (node (ref "U6") (pin "P106") (pinfunction "TDO_P106") (pintype "bidirectional"))
    )
    (net (code "154") (name "TMS") (class "Default")
      (node (ref "JP3") (pin "4") (pinfunction "4_4") (pintype "passive"))
      (node (ref "U6") (pin "P107") (pinfunction "TMS_P107") (pintype "bidirectional"))
    )
    (net (code "155") (name "UART_RX") (class "Default")
      (node (ref "JP4") (pin "3") (pinfunction "3_3") (pintype "passive"))
      (node (ref "U3") (pin "69") (pinfunction "PA10_69") (pintype "bidirectional"))
    )
    (net (code "156") (name "UART_TX") (class "Default")
      (node (ref "JP4") (pin "4") (pinfunction "4_4") (pintype "passive"))
      (node (ref "U3") (pin "68") (pinfunction "PA9_68") (pintype "bidirectional"))
    )
    (net (code "157") (name "UP") (class "Default")
      (node (ref "J2") (pin "1") (pinfunction "1_1") (pintype "passive"))
      (node (ref "U6") (pin "P78") (pinfunction "IO_L47N_1_P78") (pintype "bidirectional"))
    )
    (net (code "158") (name "VCC") (class "Default")
      (node (ref "23B") (pin "1") (pinfunction "P_1") (pintype "passive"))
      (node (ref "2A") (pin "1") (pinfunction "P_1") (pintype "passive"))
      (node (ref "C3") (pin "1") (pinfunction "1_1") (pintype "passive"))
      (node (ref "C8") (pin "2") (pinfunction "2_2") (pintype "passive"))
      (node (ref "D1") (pin "C") (pinfunction "C_C") (pintype "passive"))
      (node (ref "D2") (pin "C") (pinfunction "C_C") (pintype "passive"))
      (node (ref "D4") (pin "C") (pinfunction "C_C") (pintype "passive"))
      (node (ref "IC2") (pin "3") (pinfunction "VIN_3") (pintype "input"))
      (node (ref "IC5") (pin "3") (pinfunction "VIN_3") (pintype "input"))
      (node (ref "JP4") (pin "1") (pinfunction "1_1") (pintype "passive"))
      (node (ref "JP6") (pin "1") (pinfunction "1_1") (pintype "passive"))
      (node (ref "R11") (pin "1") (pinfunction "1_1") (pintype "passive"))
      (node (ref "R15") (pin "2") (pinfunction "2_2") (pintype "passive"))
      (node (ref "R22") (pin "2") (pinfunction "2_2") (pintype "passive"))
      (node (ref "R7") (pin "2") (pinfunction "2_2") (pintype "passive"))
      (node (ref "U1") (pin "14") (pinfunction "DPOS_14") (pintype "power_in"))
      (node (ref "U1") (pin "15") (pinfunction "VSYNC_15") (pintype "input"))
      (node (ref "U1") (pin "4") (pinfunction "APOS_4") (pintype "power_in"))
      (node (ref "U1") (pin "5") (pinfunction "ENCD_5") (pintype "input"))
      (node (ref "U2") (pin "32") (pinfunction "VCC_32") (pintype "power_in"))
      (node (ref "U5") (pin "6") (pinfunction "VDD_6") (pintype "power_in"))
    )
    (net (code "159") (name "VCC_USB") (class "Default")
      (node (ref "D2") (pin "A") (pinfunction "A_A") (pintype "passive"))
      (node (ref "J3") (pin "A4_B9") (pinfunction "VBUS_A4_B9") (pintype "power_in"))
      (node (ref "J3") (pin "B4_A9") (pinfunction "VBUS_B4_A9") (pintype "power_in"))
    )
    (net (code "160") (name "VID_CLK") (class "Default")
      (node (ref "U1") (pin "3") (pinfunction "FIN_3") (pintype "input"))
      (node (ref "U6") (pin "P56") (pinfunction "IO_L30P_GCLK1_D13_2_P56") (pintype "bidirectional"))
    )
    (net (code "161") (name "V_BLUE") (class "Default")
      (node (ref "R29") (pin "1") (pinfunction "1_1") (pintype "passive"))
      (node (ref "U6") (pin "P9") (pinfunction "IO_L50N_3_P9") (pintype "bidirectional"))
    )
    (net (code "162") (name "V_BLUE'") (class "Default")
      (node (ref "R28") (pin "1") (pinfunction "1_1") (pintype "passive"))
      (node (ref "R8") (pin "1") (pinfunction "1_1") (pintype "passive"))
      (node (ref "U1") (pin "8") (pinfunction "BIN_8") (pintype "input"))
      (node (ref "X1") (pin "7") (pinfunction "7_7") (pintype "passive"))
    )
    (net (code "163") (name "V_GREEN") (class "Default")
      (node (ref "R31") (pin "1") (pinfunction "1_1") (pintype "passive"))
      (node (ref "U6") (pin "P8") (pinfunction "IO_L51P_3_P8") (pintype "bidirectional"))
    )
    (net (code "164") (name "V_GREEN'") (class "Default")
      (node (ref "R27") (pin "1") (pinfunction "1_1") (pintype "passive"))
      (node (ref "R9") (pin "1") (pinfunction "1_1") (pintype "passive"))
      (node (ref "U1") (pin "7") (pinfunction "GIN_7") (pintype "input"))
      (node (ref "X1") (pin "11") (pinfunction "11_11") (pintype "passive"))
    )
    (net (code "165") (name "V_RED") (class "Default")
      (node (ref "R32") (pin "1") (pinfunction "1_1") (pintype "passive"))
      (node (ref "U6") (pin "P7") (pinfunction "IO_L51N_3_P7") (pintype "bidirectional"))
    )
    (net (code "166") (name "V_RED'") (class "Default")
      (node (ref "R10") (pin "1") (pinfunction "1_1") (pintype "passive"))
      (node (ref "R19") (pin "1") (pinfunction "1_1") (pintype "passive"))
      (node (ref "U1") (pin "6") (pinfunction "RIN_6") (pintype "input"))
      (node (ref "X1") (pin "15") (pinfunction "15_15") (pintype "passive"))
    )
    (net (code "167") (name "unconnected-(J2-Pad5)") (class "Default")
      (node (ref "J2") (pin "5") (pinfunction "5_5") (pintype "passive"))
    )
    (net (code "168") (name "unconnected-(J2-Pad7)") (class "Default")
      (node (ref "J2") (pin "7") (pinfunction "7_7") (pintype "passive"))
    )
    (net (code "169") (name "unconnected-(J2-Pad9)") (class "Default")
      (node (ref "J2") (pin "9") (pinfunction "9_9") (pintype "passive"))
    )
    (net (code "170") (name "unconnected-(MICRO_SD1-CD-PadCD1)") (class "Default")
      (node (ref "MICRO_SD1") (pin "CD1") (pinfunction "CD_CD1") (pintype "passive"))
    )
    (net (code "171") (name "unconnected-(MICRO_SD1-DAT1-Pad8)") (class "Default")
      (node (ref "MICRO_SD1") (pin "8") (pinfunction "DAT1_8") (pintype "bidirectional"))
    )
    (net (code "172") (name "unconnected-(MICRO_SD1-DAT2-Pad1)") (class "Default")
      (node (ref "MICRO_SD1") (pin "1") (pinfunction "DAT2_1") (pintype "bidirectional"))
    )
    (net (code "173") (name "unconnected-(U1-CRMA-Pad9)") (class "Default")
      (node (ref "U1") (pin "9") (pinfunction "CRMA_9") (pintype "output"))
    )
    (net (code "174") (name "unconnected-(U1-LUMA-Pad11)") (class "Default")
      (node (ref "U1") (pin "11") (pinfunction "LUMA_11") (pintype "output"))
    )
    (net (code "175") (name "unconnected-(U3-PB8-Pad95)") (class "Default")
      (node (ref "U3") (pin "95") (pinfunction "PB8_95") (pintype "bidirectional"))
    )
    (net (code "176") (name "unconnected-(U3-PC2-Pad17)") (class "Default")
      (node (ref "U3") (pin "17") (pinfunction "PC2_17") (pintype "bidirectional"))
    )
    (net (code "177") (name "unconnected-(U3-PC3-Pad18)") (class "Default")
      (node (ref "U3") (pin "18") (pinfunction "PC3_18") (pintype "bidirectional"))
    )
    (net (code "178") (name "unconnected-(U3-PC4-Pad33)") (class "Default")
      (node (ref "U3") (pin "33") (pinfunction "PC4_33") (pintype "bidirectional"))
    )
    (net (code "179") (name "unconnected-(U3-PC5-Pad34)") (class "Default")
      (node (ref "U3") (pin "34") (pinfunction "PC5_34") (pintype "bidirectional"))
    )
    (net (code "180") (name "unconnected-(U5-NC-Pad2)") (class "Default")
      (node (ref "U5") (pin "2") (pinfunction "NC_2") (pintype "no_connect"))
    )
    (net (code "181") (name "unconnected-(U6-CMPCS_B_2-PadP72)") (class "Default")
      (node (ref "U6") (pin "P72") (pinfunction "CMPCS_B_2_P72") (pintype "bidirectional"))
    )
    (net (code "182") (name "unconnected-(U6-DONE_2-PadP71)") (class "Default")
      (node (ref "U6") (pin "P71") (pinfunction "DONE_2_P71") (pintype "bidirectional"))
    )
    (net (code "183") (name "unconnected-(X1-Pad2)") (class "Default")
      (node (ref "X1") (pin "2") (pinfunction "2_2") (pintype "passive"))
    )
    (net (code "184") (name "unconnected-(X1-Pad6)") (class "Default")
      (node (ref "X1") (pin "6") (pinfunction "6_6") (pintype "passive"))
    )
    (net (code "185") (name "unconnected-(X1-Pad10)") (class "Default")
      (node (ref "X1") (pin "10") (pinfunction "10_10") (pintype "passive"))
    )
    (net (code "186") (name "unconnected-(X1-Pad12)") (class "Default")
      (node (ref "X1") (pin "12") (pinfunction "12_12") (pintype "passive"))
    )
    (net (code "187") (name "unconnected-(X1-Pad20)") (class "Default")
      (node (ref "X1") (pin "20") (pinfunction "20_20") (pintype "passive"))
    )
    (net (code "188") (name "{slash}BUSAK") (class "Default")
      (node (ref "18A") (pin "1") (pinfunction "P_1") (pintype "passive"))
    )
    (net (code "189") (name "{slash}BUSRQ") (class "Default")
      (node (ref "20A") (pin "1") (pinfunction "P_1") (pintype "passive"))
    )
    (net (code "190") (name "{slash}CLOCK") (class "Default")
      (node (ref "6B") (pin "1") (pinfunction "P_1") (pintype "passive"))
      (node (ref "U6") (pin "P24") (pinfunction "IO_L41P_GCLK27_3_P24") (pintype "bidirectional"))
    )
    (net (code "191") (name "{slash}HALT") (class "Default")
      (node (ref "13A") (pin "1") (pinfunction "P_1") (pintype "passive"))
      (node (ref "U6") (pin "P46") (pinfunction "IO_L49P_D3_2_P46") (pintype "bidirectional"))
    )
    (net (code "192") (name "{slash}IORQ") (class "Default")
      (node (ref "15A") (pin "1") (pinfunction "P_1") (pintype "passive"))
      (node (ref "U6") (pin "P51") (pinfunction "IO_L31P_GCLK31_D14_2_P51") (pintype "bidirectional"))
    )
    (net (code "193") (name "{slash}M1") (class "Default")
      (node (ref "22A") (pin "1") (pinfunction "P_1") (pintype "passive"))
      (node (ref "U6") (pin "P67") (pinfunction "IO_L2P_CMPCLK_2_P67") (pintype "bidirectional"))
    )
    (net (code "194") (name "{slash}MEM_OE") (class "Default")
      (node (ref "U2") (pin "24") (pinfunction "OE_24") (pintype "input"))
      (node (ref "U6") (pin "P92") (pinfunction "IO_L41N_GCLK8_1_P92") (pintype "bidirectional"))
    )
    (net (code "195") (name "{slash}MREQ") (class "Default")
      (node (ref "14A") (pin "1") (pinfunction "P_1") (pintype "passive"))
      (node (ref "U6") (pin "P48") (pinfunction "IO_L48P_D7_2_P48") (pintype "bidirectional"))
    )
    (net (code "196") (name "{slash}NMI") (class "Default")
      (node (ref "12A") (pin "1") (pinfunction "P_1") (pintype "passive"))
      (node (ref "U6") (pin "P44") (pinfunction "IO_L62P_D5_2_P44") (pintype "bidirectional"))
    )
    (net (code "197") (name "{slash}OE_OL") (class "Default")
      (node (ref "U3") (pin "47") (pinfunction "PB10_47") (pintype "bidirectional"))
      (node (ref "U6") (pin "P12") (pinfunction "IO_L49P_3_P12") (pintype "bidirectional"))
    )
    (net (code "198") (name "{slash}RD") (class "Default")
      (node (ref "16A") (pin "1") (pinfunction "P_1") (pintype "passive"))
      (node (ref "U6") (pin "P105") (pinfunction "IO_L1P_1_P105") (pintype "bidirectional"))
    )
    (net (code "199") (name "{slash}RESET") (class "Default")
      (node (ref "21A") (pin "1") (pinfunction "P_1") (pintype "passive"))
      (node (ref "U3") (pin "96") (pinfunction "PB9_96") (pintype "bidirectional"))
      (node (ref "U6") (pin "P139") (pinfunction "IO_L3N_0_P139") (pintype "bidirectional"))
    )
    (net (code "200") (name "{slash}RFSH") (class "Default")
      (node (ref "23A") (pin "1") (pinfunction "P_1") (pintype "passive"))
      (node (ref "U6") (pin "P74") (pinfunction "IO_L74N_DOUT_BUSY_1_P74") (pintype "bidirectional"))
    )
    (net (code "201") (name "{slash}WAIT") (class "Default")
      (node (ref "19A") (pin "1") (pinfunction "P_1") (pintype "passive"))
      (node (ref "U3") (pin "23") (pinfunction "PA0_23") (pintype "bidirectional"))
    )
    (net (code "202") (name "{slash}WR") (class "Default")
      (node (ref "17A") (pin "1") (pinfunction "P_1") (pintype "passive"))
      (node (ref "U6") (pin "P58") (pinfunction "IO_L14P_D11_2_P58") (pintype "bidirectional"))
    )
    (net (code "203") (name "{slash}WR'") (class "Default")
      (node (ref "U2") (pin "29") (pinfunction "WE_29") (pintype "input"))
      (node (ref "U3") (pin "26") (pinfunction "PA3_26") (pintype "bidirectional"))
      (node (ref "U6") (pin "P102") (pinfunction "IO_L32P_1_P102") (pintype "bidirectional"))
    )
  )
)
